# schematic.net
KiCad netlist of a schematic drawn in EasyEDA
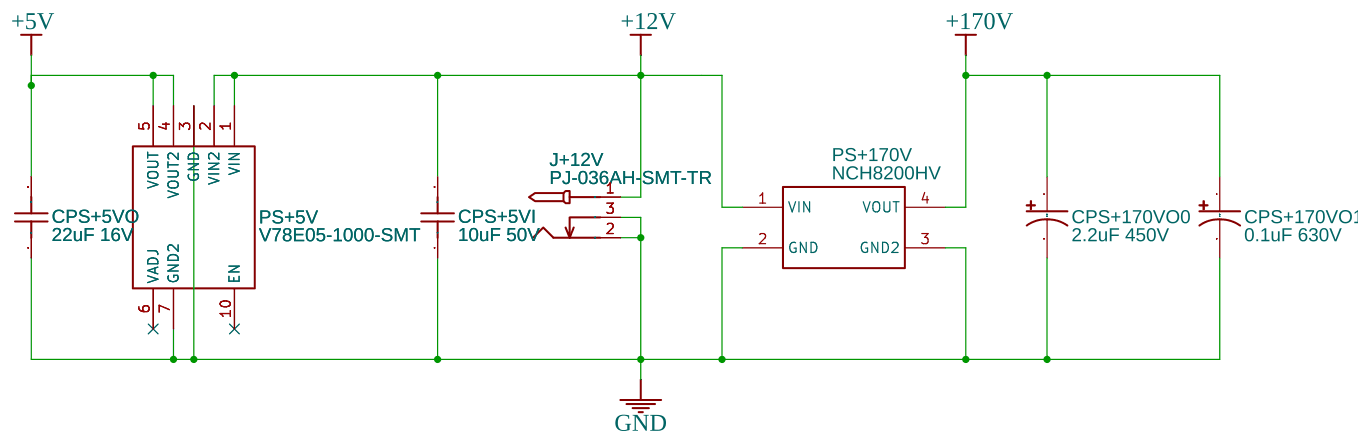
[diagram p0: power]
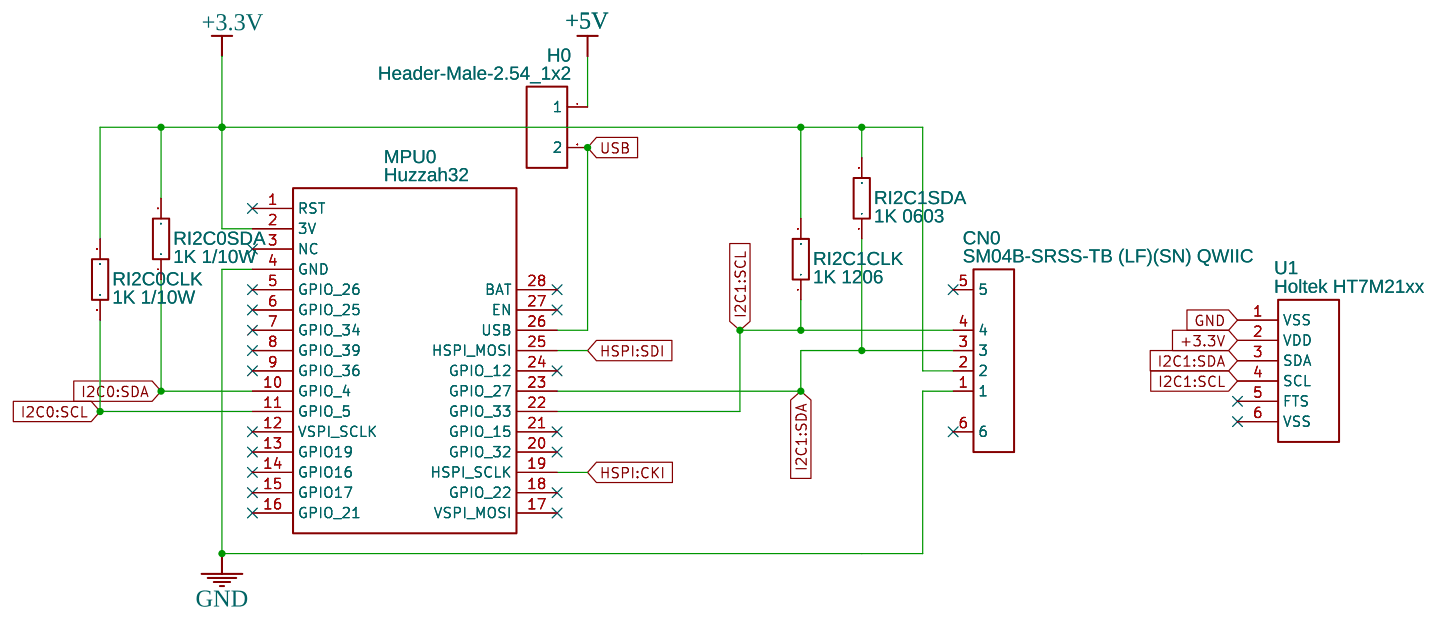
[diagram p1: smarts]
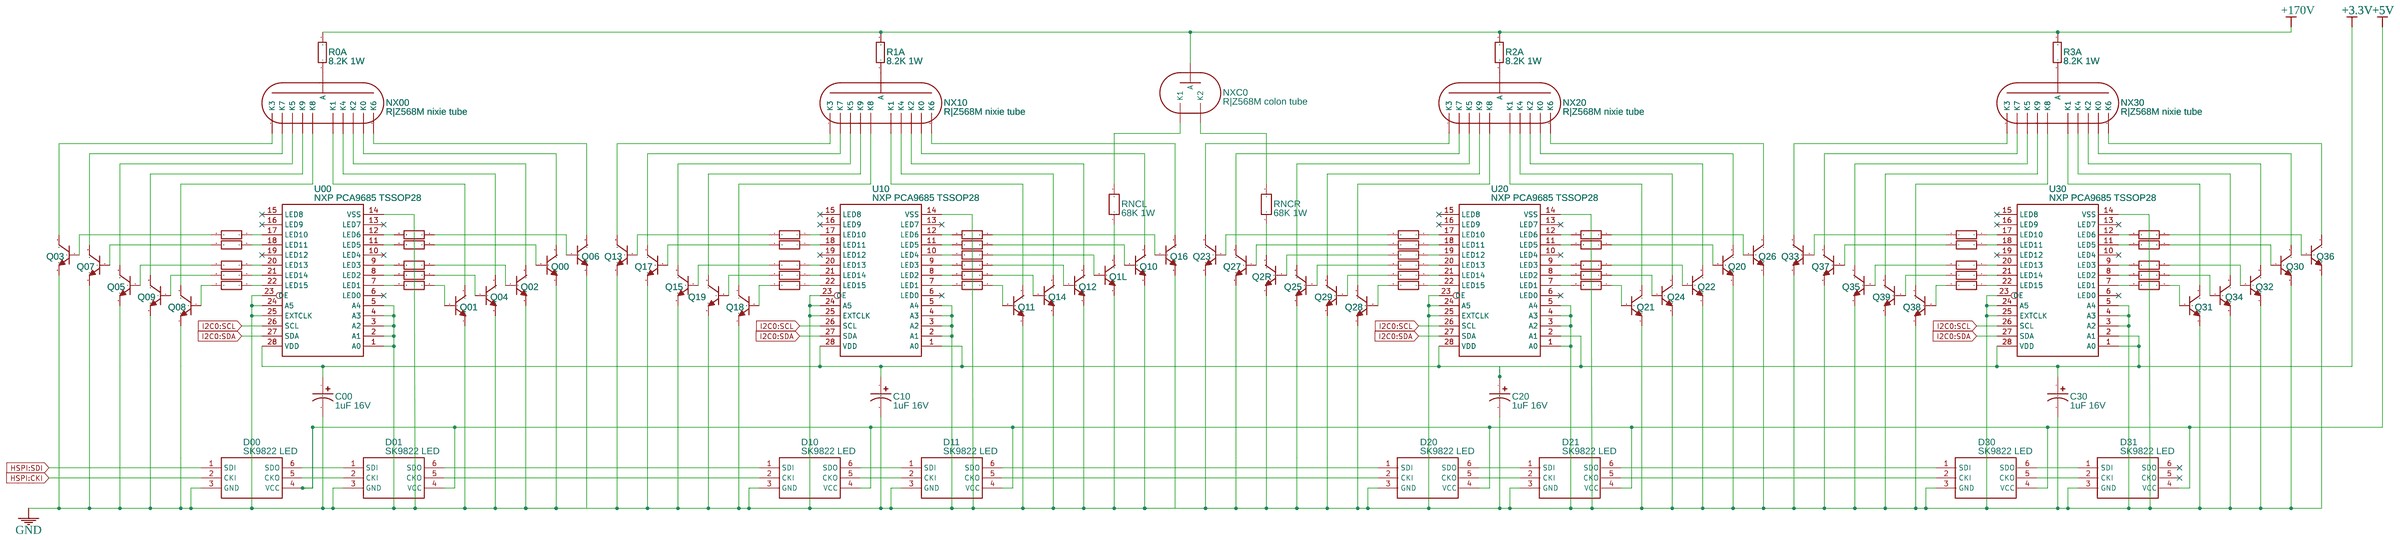
[diagram p2: nixies]

(export (version "E")
  (design (tool "Eeschema 10.0.6"))
  (components
    (comp (ref "CPS+5VI")
      (value "10uF 50V")
      (fields
        (field (name "BOM_Manufacturer Part") "C1210C106K5RACTU")
        (field (name "BOM_Supplier Part") "399-11629-1-ND")
      )
      (libsource (lib "") (part "CL32Y106KBJ4PNE"))
    )
    (comp (ref "CPS+5VO")
      (value "22uF 16V")
      (fields
        (field (name "BOM_Manufacturer Part") "C1210C226K4RAC7800")
        (field (name "BOM_Supplier Part") "399-11662-1-ND")
      )
      (libsource (lib "") (part "CL32A226KOJNNWE"))
    )
    (comp (ref "CPS+170VO0")
      (value "2.2uF 450V")
      (fields
        (field (name "BOM_Manufacturer Part") "C5750X6S2W225K250KA")
        (field (name "BOM_Supplier Part") "445-7781-1-ND")
      )
      (libsource (lib "") (part "ULV2G100MNL1GS_1"))
    )
    (comp (ref "CPS+170VO1")
      (value "0.1uF 630V")
      (fields
        (field (name "BOM_Manufacturer Part") "CGA8N4X7R2J104K230KA")
        (field (name "BOM_Supplier Part") "445-7922-1-ND")
      )
      (libsource (lib "") (part "ULV2G100MNL1GS"))
    )
    (comp (ref "J+12V")
      (value "PJ-036AH-SMT-TR")
      (fields (field (name "BOM_Supplier Part") "CP-036AHPJCT-ND"))
      (libsource (lib "") (part "DC005-2.0MM"))
    )
    (comp (ref "PS+5V")
      (value "V78E05-1000-SMT")
      (fields (field (name "BOM_Supplier Part") "102-5033-1-ND"))
      (libsource (lib "") (part "V78E05-1000-SMT"))
    )
    (comp (ref "PS+170V")
      (value "NCH8200HV")
      (fields (field (name "BOM_Supplier Part") "B074S2T7X3"))
      (libsource (lib "") (part "NCH8200HV"))
    )
    (comp (ref "CN0")
      (value "SM04B-SRSS-TB (LF)(SN) QWIIC")
      (fields
        (field (name "BOM_Manufacturer Part") "PRT-14417")
        (field (name "BOM_Supplier Part") "PRT-14417-ND")
      )
      (libsource (lib "") (part "SM04B-SRSS-TB (LF)(SN) QWIIC"))
    )
    (comp (ref "H0")
      (value "Header-Male-2.54_1x2")
      (fields
        (field (name "BOM_Manufacturer Part") "M20-8890245")
        (field (name "BOM_Supplier Part") "952-3231-ND")
      )
      (libsource (lib "") (part "Header-Male-2.54_1x2"))
    )
    (comp (ref "MPU0")
      (value "Huzzah32")
      (fields (field (name "BOM_Manufacturer Part") "3405") (field (name "BOM_Supplier Part") "1528-2181-ND"))
      (libsource (lib "") (part "Huzzah32"))
    )
    (comp (ref "RI2C0CLK")
      (value "1K 1/10W")
      (fields
        (field (name "BOM_Manufacturer Part") "CRCW06031K00FKEA")
        (field (name "BOM_Supplier Part") "541-1.00KHCT-ND")
      )
      (libsource (lib "") (part "CR0805-FX-1001ELF"))
    )
    (comp (ref "RI2C0SDA")
      (value "1K 1/10W")
      (fields
        (field (name "BOM_Manufacturer Part") "CRCW06031K00FKEA")
        (field (name "BOM_Supplier Part") "541-1.00KHCT-ND")
      )
      (libsource (lib "") (part "CR0805-FX-1001ELF_1"))
    )
    (comp (ref "RI2C1CLK")
      (value "1K 1206")
      (fields
        (field (name "BOM_Manufacturer Part") "RCL06121K00FKEA")
        (field (name "BOM_Supplier Part") "RCL1.00KCCT-ND")
      )
      (libsource (lib "") (part "CR0805-FX-1001ELF_3"))
    )
    (comp (ref "RI2C1SDA")
      (value "1K 0603")
      (fields
        (field (name "BOM_Manufacturer Part") "CRCW06031K00FKEA")
        (field (name "BOM_Supplier Part") "541-1.00KHCT-ND")
      )
      (libsource (lib "") (part "CR0805-FX-1001ELF_2"))
    )
    (comp (ref "U1")
      (value "Holtek HT7M21xx")
      (fields (field (name "BOM_Manufacturer Part") "HT7M21xx"))
      (libsource (lib "") (part "Holtek HT7M21xx"))
    )
    (comp (ref "C00")
      (value "1uF 16V")
      (fields
        (field (name "BOM_Manufacturer Part") "C0603C105K8RACTU")
        (field (name "BOM_Supplier Part") "399-11133-1-ND")
      )
      (libsource (lib "") (part "C_Tan_SMD_A_US"))
    )
    (comp (ref "C10")
      (value "1uF 16V")
      (fields
        (field (name "BOM_Manufacturer Part") "C0603C105K8RACTU")
        (field (name "BOM_Supplier Part") "399-11133-1-ND")
      )
      (libsource (lib "") (part "C_Tan_SMD_A_US"))
    )
    (comp (ref "C20")
      (value "1uF 16V")
      (fields
        (field (name "BOM_Manufacturer Part") "C0603C105K8RACTU")
        (field (name "BOM_Supplier Part") "399-11133-1-ND")
      )
      (libsource (lib "") (part "C_Tan_SMD_A_US_1"))
    )
    (comp (ref "C30")
      (value "1uF 16V")
      (fields
        (field (name "BOM_Manufacturer Part") "C0603C105K8RACTU")
        (field (name "BOM_Supplier Part") "399-11133-1-ND")
      )
      (libsource (lib "") (part "C_Tan_SMD_A_US"))
    )
    (comp (ref "D00")
      (value "SK9822 LED")
      (fields (field (name "BOM_Manufacturer Part") "2343") (field (name "BOM_Supplier Part") "1528-1436-ND"))
      (libsource (lib "") (part "SK9822 LED_1"))
    )
    (comp (ref "D01")
      (value "SK9822 LED")
      (fields (field (name "BOM_Manufacturer Part") "2343") (field (name "BOM_Supplier Part") "1528-1436-ND"))
      (libsource (lib "") (part "SK9822 LED_1"))
    )
    (comp (ref "D10")
      (value "SK9822 LED")
      (fields (field (name "BOM_Manufacturer Part") "2343") (field (name "BOM_Supplier Part") "1528-1436-ND"))
      (libsource (lib "") (part "SK9822 LED_1"))
    )
    (comp (ref "D11")
      (value "SK9822 LED")
      (fields (field (name "BOM_Manufacturer Part") "2343") (field (name "BOM_Supplier Part") "1528-1436-ND"))
      (libsource (lib "") (part "SK9822 LED_1"))
    )
    (comp (ref "D20")
      (value "SK9822 LED")
      (fields (field (name "BOM_Manufacturer Part") "2343") (field (name "BOM_Supplier Part") "1528-1436-ND"))
      (libsource (lib "") (part "SK9822 LED"))
    )
    (comp (ref "D21")
      (value "SK9822 LED")
      (fields (field (name "BOM_Manufacturer Part") "2343") (field (name "BOM_Supplier Part") "1528-1436-ND"))
      (libsource (lib "") (part "SK9822 LED"))
    )
    (comp (ref "D30")
      (value "SK9822 LED")
      (fields (field (name "BOM_Manufacturer Part") "2343") (field (name "BOM_Supplier Part") "1528-1436-ND"))
      (libsource (lib "") (part "SK9822 LED"))
    )
    (comp (ref "D31")
      (value "SK9822 LED")
      (fields (field (name "BOM_Manufacturer Part") "2343") (field (name "BOM_Supplier Part") "1528-1436-ND"))
      (libsource (lib "") (part "SK9822 LED"))
    )
    (comp (ref "NX00") (value "R|Z568M nixie tube") (libsource (lib "") (part "R|Z568M nixie tube")))
    (comp (ref "NX10") (value "R|Z568M nixie tube") (libsource (lib "") (part "R|Z568M nixie tube")))
    (comp (ref "NX20") (value "R|Z568M nixie tube") (libsource (lib "") (part "R|Z568M nixie tube")))
    (comp (ref "NX30") (value "R|Z568M nixie tube") (libsource (lib "") (part "R|Z568M nixie tube")))
    (comp (ref "NXC0") (value "R|Z568M colon tube") (libsource (lib "") (part "R|Z568M colon tube")))
    (comp (ref "Q00")
      (value "SMMBTA42LT1G")
      (fields (field (name "BOM_Supplier Part") "SMMBTA42LT1GOSCT-ND"))
      (libsource (lib "") (part "MMBTA42LT1G"))
    )
    (comp (ref "Q01")
      (value "SMMBTA42LT1G")
      (fields (field (name "BOM_Supplier Part") "SMMBTA42LT1GOSCT-ND"))
      (libsource (lib "") (part "MMBTA42LT1G"))
    )
    (comp (ref "Q1L")
      (value "SMMBTA42LT1G")
      (fields (field (name "BOM_Supplier Part") "SMMBTA42LT1GOSCT-ND"))
      (libsource (lib "") (part "MMBTA42LT1G_5"))
    )
    (comp (ref "Q02")
      (value "SMMBTA42LT1G")
      (fields (field (name "BOM_Supplier Part") "SMMBTA42LT1GOSCT-ND"))
      (libsource (lib "") (part "MMBTA42LT1G"))
    )
    (comp (ref "Q2R")
      (value "SMMBTA42LT1G")
      (fields (field (name "BOM_Supplier Part") "SMMBTA42LT1GOSCT-ND"))
      (libsource (lib "") (part "MMBTA42LT1G_3"))
    )
    (comp (ref "Q03")
      (value "SMMBTA42LT1G")
      (fields (field (name "BOM_Supplier Part") "SMMBTA42LT1GOSCT-ND"))
      (libsource (lib "") (part "MMBTA42LT1G_1"))
    )
    (comp (ref "Q04")
      (value "SMMBTA42LT1G")
      (fields (field (name "BOM_Supplier Part") "SMMBTA42LT1GOSCT-ND"))
      (libsource (lib "") (part "MMBTA42LT1G"))
    )
    (comp (ref "Q05")
      (value "SMMBTA42LT1G")
      (fields (field (name "BOM_Supplier Part") "SMMBTA42LT1GOSCT-ND"))
      (libsource (lib "") (part "MMBTA42LT1G_1"))
    )
    (comp (ref "Q06")
      (value "SMMBTA42LT1G")
      (fields (field (name "BOM_Supplier Part") "SMMBTA42LT1GOSCT-ND"))
      (libsource (lib "") (part "MMBTA42LT1G"))
    )
    (comp (ref "Q07")
      (value "SMMBTA42LT1G")
      (fields (field (name "BOM_Supplier Part") "SMMBTA42LT1GOSCT-ND"))
      (libsource (lib "") (part "MMBTA42LT1G_1"))
    )
    (comp (ref "Q08")
      (value "SMMBTA42LT1G")
      (fields (field (name "BOM_Supplier Part") "SMMBTA42LT1GOSCT-ND"))
      (libsource (lib "") (part "MMBTA42LT1G_1"))
    )
    (comp (ref "Q09")
      (value "SMMBTA42LT1G")
      (fields (field (name "BOM_Supplier Part") "SMMBTA42LT1GOSCT-ND"))
      (libsource (lib "") (part "MMBTA42LT1G_1"))
    )
    (comp (ref "Q10")
      (value "SMMBTA42LT1G")
      (fields (field (name "BOM_Supplier Part") "SMMBTA42LT1GOSCT-ND"))
      (libsource (lib "") (part "MMBTA42LT1G"))
    )
    (comp (ref "Q11")
      (value "SMMBTA42LT1G")
      (fields (field (name "BOM_Supplier Part") "SMMBTA42LT1GOSCT-ND"))
      (libsource (lib "") (part "MMBTA42LT1G"))
    )
    (comp (ref "Q12")
      (value "SMMBTA42LT1G")
      (fields (field (name "BOM_Supplier Part") "SMMBTA42LT1GOSCT-ND"))
      (libsource (lib "") (part "MMBTA42LT1G"))
    )
    (comp (ref "Q13")
      (value "SMMBTA42LT1G")
      (fields (field (name "BOM_Supplier Part") "SMMBTA42LT1GOSCT-ND"))
      (libsource (lib "") (part "MMBTA42LT1G_1"))
    )
    (comp (ref "Q14")
      (value "SMMBTA42LT1G")
      (fields (field (name "BOM_Supplier Part") "SMMBTA42LT1GOSCT-ND"))
      (libsource (lib "") (part "MMBTA42LT1G"))
    )
    (comp (ref "Q15")
      (value "SMMBTA42LT1G")
      (fields (field (name "BOM_Supplier Part") "SMMBTA42LT1GOSCT-ND"))
      (libsource (lib "") (part "MMBTA42LT1G_1"))
    )
    (comp (ref "Q16")
      (value "SMMBTA42LT1G")
      (fields (field (name "BOM_Supplier Part") "SMMBTA42LT1GOSCT-ND"))
      (libsource (lib "") (part "MMBTA42LT1G"))
    )
    (comp (ref "Q17")
      (value "SMMBTA42LT1G")
      (fields (field (name "BOM_Supplier Part") "SMMBTA42LT1GOSCT-ND"))
      (libsource (lib "") (part "MMBTA42LT1G_1"))
    )
    (comp (ref "Q18")
      (value "SMMBTA42LT1G")
      (fields (field (name "BOM_Supplier Part") "SMMBTA42LT1GOSCT-ND"))
      (libsource (lib "") (part "MMBTA42LT1G_1"))
    )
    (comp (ref "Q19")
      (value "SMMBTA42LT1G")
      (fields (field (name "BOM_Supplier Part") "SMMBTA42LT1GOSCT-ND"))
      (libsource (lib "") (part "MMBTA42LT1G_1"))
    )
    (comp (ref "Q20")
      (value "SMMBTA42LT1G")
      (fields (field (name "BOM_Supplier Part") "SMMBTA42LT1GOSCT-ND"))
      (libsource (lib "") (part "MMBTA42LT1G_2"))
    )
    (comp (ref "Q21")
      (value "SMMBTA42LT1G")
      (fields (field (name "BOM_Supplier Part") "SMMBTA42LT1GOSCT-ND"))
      (libsource (lib "") (part "MMBTA42LT1G_2"))
    )
    (comp (ref "Q22")
      (value "SMMBTA42LT1G")
      (fields (field (name "BOM_Supplier Part") "SMMBTA42LT1GOSCT-ND"))
      (libsource (lib "") (part "MMBTA42LT1G_2"))
    )
    (comp (ref "Q23")
      (value "SMMBTA42LT1G")
      (fields (field (name "BOM_Supplier Part") "SMMBTA42LT1GOSCT-ND"))
      (libsource (lib "") (part "MMBTA42LT1G_1"))
    )
    (comp (ref "Q24")
      (value "SMMBTA42LT1G")
      (fields (field (name "BOM_Supplier Part") "SMMBTA42LT1GOSCT-ND"))
      (libsource (lib "") (part "MMBTA42LT1G_2"))
    )
    (comp (ref "Q25")
      (value "SMMBTA42LT1G")
      (fields (field (name "BOM_Supplier Part") "SMMBTA42LT1GOSCT-ND"))
      (libsource (lib "") (part "MMBTA42LT1G_4"))
    )
    (comp (ref "Q26")
      (value "SMMBTA42LT1G")
      (fields (field (name "BOM_Supplier Part") "SMMBTA42LT1GOSCT-ND"))
      (libsource (lib "") (part "MMBTA42LT1G_2"))
    )
    (comp (ref "Q27")
      (value "SMMBTA42LT1G")
      (fields (field (name "BOM_Supplier Part") "SMMBTA42LT1GOSCT-ND"))
      (libsource (lib "") (part "MMBTA42LT1G_1"))
    )
    (comp (ref "Q28")
      (value "SMMBTA42LT1G")
      (fields (field (name "BOM_Supplier Part") "SMMBTA42LT1GOSCT-ND"))
      (libsource (lib "") (part "MMBTA42LT1G_4"))
    )
    (comp (ref "Q29")
      (value "SMMBTA42LT1G")
      (fields (field (name "BOM_Supplier Part") "SMMBTA42LT1GOSCT-ND"))
      (libsource (lib "") (part "MMBTA42LT1G_4"))
    )
    (comp (ref "Q30")
      (value "SMMBTA42LT1G")
      (fields (field (name "BOM_Supplier Part") "SMMBTA42LT1GOSCT-ND"))
      (libsource (lib "") (part "MMBTA42LT1G_2"))
    )
    (comp (ref "Q31")
      (value "SMMBTA42LT1G")
      (fields (field (name "BOM_Supplier Part") "SMMBTA42LT1GOSCT-ND"))
      (libsource (lib "") (part "MMBTA42LT1G_2"))
    )
    (comp (ref "Q32")
      (value "SMMBTA42LT1G")
      (fields (field (name "BOM_Supplier Part") "SMMBTA42LT1GOSCT-ND"))
      (libsource (lib "") (part "MMBTA42LT1G_2"))
    )
    (comp (ref "Q33")
      (value "SMMBTA42LT1G")
      (fields (field (name "BOM_Supplier Part") "SMMBTA42LT1GOSCT-ND"))
      (libsource (lib "") (part "MMBTA42LT1G_4"))
    )
    (comp (ref "Q34")
      (value "SMMBTA42LT1G")
      (fields (field (name "BOM_Supplier Part") "SMMBTA42LT1GOSCT-ND"))
      (libsource (lib "") (part "MMBTA42LT1G_2"))
    )
    (comp (ref "Q35")
      (value "SMMBTA42LT1G")
      (fields (field (name "BOM_Supplier Part") "SMMBTA42LT1GOSCT-ND"))
      (libsource (lib "") (part "MMBTA42LT1G_4"))
    )
    (comp (ref "Q36")
      (value "SMMBTA42LT1G")
      (fields (field (name "BOM_Supplier Part") "SMMBTA42LT1GOSCT-ND"))
      (libsource (lib "") (part "MMBTA42LT1G_2"))
    )
    (comp (ref "Q37")
      (value "SMMBTA42LT1G")
      (fields (field (name "BOM_Supplier Part") "SMMBTA42LT1GOSCT-ND"))
      (libsource (lib "") (part "MMBTA42LT1G_4"))
    )
    (comp (ref "Q38")
      (value "SMMBTA42LT1G")
      (fields (field (name "BOM_Supplier Part") "SMMBTA42LT1GOSCT-ND"))
      (libsource (lib "") (part "MMBTA42LT1G_4"))
    )
    (comp (ref "Q39")
      (value "SMMBTA42LT1G")
      (fields (field (name "BOM_Supplier Part") "SMMBTA42LT1GOSCT-ND"))
      (libsource (lib "") (part "MMBTA42LT1G_4"))
    )
    (comp (ref "R00")
      (value "1K 1/10W")
      (fields
        (field (name "BOM_Manufacturer Part") "CRCW06031K00FKEA")
        (field (name "BOM_Supplier Part") "541-1.00KHCT-ND")
      )
      (libsource (lib "") (part "CR0805-FX-1001ELF"))
    )
    (comp (ref "R0A")
      (value "8.2K 1W")
      (fields
        (field (name "BOM_Manufacturer Part") "CRCW25128K20JNEG")
        (field (name "BOM_Supplier Part") "541-8.2KXCT-ND")
      )
      (libsource (lib "") (part "CR2512F8K2E04_3"))
    )
    (comp (ref "R01")
      (value "1K 1/10W")
      (fields
        (field (name "BOM_Manufacturer Part") "CRCW06031K00FKEA")
        (field (name "BOM_Supplier Part") "541-1.00KHCT-ND")
      )
      (libsource (lib "") (part "CR0805-FX-1001ELF"))
    )
    (comp (ref "R1A")
      (value "8.2K 1W")
      (fields
        (field (name "BOM_Manufacturer Part") "CRCW25128K20JNEG")
        (field (name "BOM_Supplier Part") "541-8.2KXCT-ND")
      )
      (libsource (lib "") (part "CR2512F8K2E04"))
    )
    (comp (ref "R1L")
      (value "1K 1/10W")
      (fields
        (field (name "BOM_Manufacturer Part") "CRCW06031K00FKEA")
        (field (name "BOM_Supplier Part") "541-1.00KHCT-ND")
      )
      (libsource (lib "") (part "CR0805-FX-1001ELF_1"))
    )
    (comp (ref "R02")
      (value "1K 1/10W")
      (fields
        (field (name "BOM_Manufacturer Part") "CRCW06031K00FKEA")
        (field (name "BOM_Supplier Part") "541-1.00KHCT-ND")
      )
      (libsource (lib "") (part "CR0805-FX-1001ELF"))
    )
    (comp (ref "R2A")
      (value "8.2K 1W")
      (fields
        (field (name "BOM_Manufacturer Part") "CRCW25128K20JNEG")
        (field (name "BOM_Supplier Part") "541-8.2KXCT-ND")
      )
      (libsource (lib "") (part "CR2512F8K2E04_2"))
    )
    (comp (ref "R2R")
      (value "1K 1/10W")
      (fields
        (field (name "BOM_Manufacturer Part") "CRCW06031K00FKEA")
        (field (name "BOM_Supplier Part") "541-1.00KHCT-ND")
      )
      (libsource (lib "") (part "CR0805-FX-1001ELF_2"))
    )
    (comp (ref "R03")
      (value "1K 1/10W")
      (fields
        (field (name "BOM_Manufacturer Part") "CRCW06031K00FKEA")
        (field (name "BOM_Supplier Part") "541-1.00KHCT-ND")
      )
      (libsource (lib "") (part "CR0805-FX-1001ELF"))
    )
    (comp (ref "R3A")
      (value "8.2K 1W")
      (fields
        (field (name "BOM_Manufacturer Part") "CRCW25128K20JNEG")
        (field (name "BOM_Supplier Part") "541-8.2KXCT-ND")
      )
      (libsource (lib "") (part "CR2512F8K2E04_1"))
    )
    (comp (ref "R04")
      (value "1K 1/10W")
      (fields
        (field (name "BOM_Manufacturer Part") "CRCW06031K00FKEA")
        (field (name "BOM_Supplier Part") "541-1.00KHCT-ND")
      )
      (libsource (lib "") (part "CR0805-FX-1001ELF"))
    )
    (comp (ref "R05")
      (value "1K 1/10W")
      (fields
        (field (name "BOM_Manufacturer Part") "CRCW06031K00FKEA")
        (field (name "BOM_Supplier Part") "541-1.00KHCT-ND")
      )
      (libsource (lib "") (part "CR0805-FX-1001ELF"))
    )
    (comp (ref "R06")
      (value "1K 1/10W")
      (fields
        (field (name "BOM_Manufacturer Part") "CRCW06031K00FKEA")
        (field (name "BOM_Supplier Part") "541-1.00KHCT-ND")
      )
      (libsource (lib "") (part "CR0805-FX-1001ELF"))
    )
    (comp (ref "R07")
      (value "1K 1/10W")
      (fields
        (field (name "BOM_Manufacturer Part") "CRCW06031K00FKEA")
        (field (name "BOM_Supplier Part") "541-1.00KHCT-ND")
      )
      (libsource (lib "") (part "CR0805-FX-1001ELF"))
    )
    (comp (ref "R08")
      (value "1K 1/10W")
      (fields
        (field (name "BOM_Manufacturer Part") "CRCW06031K00FKEA")
        (field (name "BOM_Supplier Part") "541-1.00KHCT-ND")
      )
      (libsource (lib "") (part "CR0805-FX-1001ELF"))
    )
    (comp (ref "R09")
      (value "1K 1/10W")
      (fields
        (field (name "BOM_Manufacturer Part") "CRCW06031K00FKEA")
        (field (name "BOM_Supplier Part") "541-1.00KHCT-ND")
      )
      (libsource (lib "") (part "CR0805-FX-1001ELF"))
    )
    (comp (ref "R10")
      (value "1K 1/10W")
      (fields
        (field (name "BOM_Manufacturer Part") "CRCW06031K00FKEA")
        (field (name "BOM_Supplier Part") "541-1.00KHCT-ND")
      )
      (libsource (lib "") (part "CR0805-FX-1001ELF"))
    )
    (comp (ref "R11")
      (value "1K 1/10W")
      (fields
        (field (name "BOM_Manufacturer Part") "CRCW06031K00FKEA")
        (field (name "BOM_Supplier Part") "541-1.00KHCT-ND")
      )
      (libsource (lib "") (part "CR0805-FX-1001ELF"))
    )
    (comp (ref "R12")
      (value "1K 1/10W")
      (fields
        (field (name "BOM_Manufacturer Part") "CRCW06031K00FKEA")
        (field (name "BOM_Supplier Part") "541-1.00KHCT-ND")
      )
      (libsource (lib "") (part "CR0805-FX-1001ELF"))
    )
    (comp (ref "R13")
      (value "1K 1/10W")
      (fields
        (field (name "BOM_Manufacturer Part") "CRCW06031K00FKEA")
        (field (name "BOM_Supplier Part") "541-1.00KHCT-ND")
      )
      (libsource (lib "") (part "CR0805-FX-1001ELF"))
    )
    (comp (ref "R14")
      (value "1K 1/10W")
      (fields
        (field (name "BOM_Manufacturer Part") "CRCW06031K00FKEA")
        (field (name "BOM_Supplier Part") "541-1.00KHCT-ND")
      )
      (libsource (lib "") (part "CR0805-FX-1001ELF"))
    )
    (comp (ref "R15")
      (value "1K 1/10W")
      (fields
        (field (name "BOM_Manufacturer Part") "CRCW06031K00FKEA")
        (field (name "BOM_Supplier Part") "541-1.00KHCT-ND")
      )
      (libsource (lib "") (part "CR0805-FX-1001ELF"))
    )
    (comp (ref "R16")
      (value "1K 1/10W")
      (fields
        (field (name "BOM_Manufacturer Part") "CRCW06031K00FKEA")
        (field (name "BOM_Supplier Part") "541-1.00KHCT-ND")
      )
      (libsource (lib "") (part "CR0805-FX-1001ELF"))
    )
    (comp (ref "R17")
      (value "1K 1/10W")
      (fields
        (field (name "BOM_Manufacturer Part") "CRCW06031K00FKEA")
        (field (name "BOM_Supplier Part") "541-1.00KHCT-ND")
      )
      (libsource (lib "") (part "CR0805-FX-1001ELF"))
    )
    (comp (ref "R18")
      (value "1K 1/10W")
      (fields
        (field (name "BOM_Manufacturer Part") "CRCW06031K00FKEA")
        (field (name "BOM_Supplier Part") "541-1.00KHCT-ND")
      )
      (libsource (lib "") (part "CR0805-FX-1001ELF"))
    )
    (comp (ref "R19")
      (value "1K 1/10W")
      (fields
        (field (name "BOM_Manufacturer Part") "CRCW06031K00FKEA")
        (field (name "BOM_Supplier Part") "541-1.00KHCT-ND")
      )
      (libsource (lib "") (part "CR0805-FX-1001ELF"))
    )
    (comp (ref "R20")
      (value "1K 1/10W")
      (fields
        (field (name "BOM_Manufacturer Part") "CRCW06031K00FKEA")
        (field (name "BOM_Supplier Part") "541-1.00KHCT-ND")
      )
      (libsource (lib "") (part "CR0805-FX-1001ELF"))
    )
    (comp (ref "R21")
      (value "1K 1/10W")
      (fields
        (field (name "BOM_Manufacturer Part") "CRCW06031K00FKEA")
        (field (name "BOM_Supplier Part") "541-1.00KHCT-ND")
      )
      (libsource (lib "") (part "CR0805-FX-1001ELF"))
    )
    (comp (ref "R22")
      (value "1K 1/10W")
      (fields
        (field (name "BOM_Manufacturer Part") "CRCW06031K00FKEA")
        (field (name "BOM_Supplier Part") "541-1.00KHCT-ND")
      )
      (libsource (lib "") (part "CR0805-FX-1001ELF"))
    )
    (comp (ref "R23")
      (value "1K 1/10W")
      (fields
        (field (name "BOM_Manufacturer Part") "CRCW06031K00FKEA")
        (field (name "BOM_Supplier Part") "541-1.00KHCT-ND")
      )
      (libsource (lib "") (part "CR0805-FX-1001ELF"))
    )
    (comp (ref "R24")
      (value "1K 1/10W")
      (fields
        (field (name "BOM_Manufacturer Part") "CRCW06031K00FKEA")
        (field (name "BOM_Supplier Part") "541-1.00KHCT-ND")
      )
      (libsource (lib "") (part "CR0805-FX-1001ELF"))
    )
    (comp (ref "R25")
      (value "1K 1/10W")
      (fields
        (field (name "BOM_Manufacturer Part") "CRCW06031K00FKEA")
        (field (name "BOM_Supplier Part") "541-1.00KHCT-ND")
      )
      (libsource (lib "") (part "CR0805-FX-1001ELF"))
    )
    (comp (ref "R26")
      (value "1K 1/10W")
      (fields
        (field (name "BOM_Manufacturer Part") "CRCW06031K00FKEA")
        (field (name "BOM_Supplier Part") "541-1.00KHCT-ND")
      )
      (libsource (lib "") (part "CR0805-FX-1001ELF"))
    )
    (comp (ref "R27")
      (value "1K 1/10W")
      (fields
        (field (name "BOM_Manufacturer Part") "CRCW06031K00FKEA")
        (field (name "BOM_Supplier Part") "541-1.00KHCT-ND")
      )
      (libsource (lib "") (part "CR0805-FX-1001ELF"))
    )
    (comp (ref "R28")
      (value "1K 1/10W")
      (fields
        (field (name "BOM_Manufacturer Part") "CRCW06031K00FKEA")
        (field (name "BOM_Supplier Part") "541-1.00KHCT-ND")
      )
      (libsource (lib "") (part "CR0805-FX-1001ELF"))
    )
    (comp (ref "R29")
      (value "1K 1/10W")
      (fields
        (field (name "BOM_Manufacturer Part") "CRCW06031K00FKEA")
        (field (name "BOM_Supplier Part") "541-1.00KHCT-ND")
      )
      (libsource (lib "") (part "CR0805-FX-1001ELF"))
    )
    (comp (ref "R30")
      (value "1K 1/10W")
      (fields
        (field (name "BOM_Manufacturer Part") "CRCW06031K00FKEA")
        (field (name "BOM_Supplier Part") "541-1.00KHCT-ND")
      )
      (libsource (lib "") (part "CR0805-FX-1001ELF"))
    )
    (comp (ref "R31")
      (value "1K 1/10W")
      (fields
        (field (name "BOM_Manufacturer Part") "CRCW06031K00FKEA")
        (field (name "BOM_Supplier Part") "541-1.00KHCT-ND")
      )
      (libsource (lib "") (part "CR0805-FX-1001ELF"))
    )
    (comp (ref "R32")
      (value "1K 1/10W")
      (fields
        (field (name "BOM_Manufacturer Part") "CRCW06031K00FKEA")
        (field (name "BOM_Supplier Part") "541-1.00KHCT-ND")
      )
      (libsource (lib "") (part "CR0805-FX-1001ELF"))
    )
    (comp (ref "R33")
      (value "1K 1/10W")
      (fields
        (field (name "BOM_Manufacturer Part") "CRCW06031K00FKEA")
        (field (name "BOM_Supplier Part") "541-1.00KHCT-ND")
      )
      (libsource (lib "") (part "CR0805-FX-1001ELF"))
    )
    (comp (ref "R34")
      (value "1K 1/10W")
      (fields
        (field (name "BOM_Manufacturer Part") "CRCW06031K00FKEA")
        (field (name "BOM_Supplier Part") "541-1.00KHCT-ND")
      )
      (libsource (lib "") (part "CR0805-FX-1001ELF"))
    )
    (comp (ref "R35")
      (value "1K 1/10W")
      (fields
        (field (name "BOM_Manufacturer Part") "CRCW06031K00FKEA")
        (field (name "BOM_Supplier Part") "541-1.00KHCT-ND")
      )
      (libsource (lib "") (part "CR0805-FX-1001ELF"))
    )
    (comp (ref "R36")
      (value "1K 1/10W")
      (fields
        (field (name "BOM_Manufacturer Part") "CRCW06031K00FKEA")
        (field (name "BOM_Supplier Part") "541-1.00KHCT-ND")
      )
      (libsource (lib "") (part "CR0805-FX-1001ELF"))
    )
    (comp (ref "R37")
      (value "1K 1/10W")
      (fields
        (field (name "BOM_Manufacturer Part") "CRCW06031K00FKEA")
        (field (name "BOM_Supplier Part") "541-1.00KHCT-ND")
      )
      (libsource (lib "") (part "CR0805-FX-1001ELF"))
    )
    (comp (ref "R38")
      (value "1K 1/10W")
      (fields
        (field (name "BOM_Manufacturer Part") "CRCW06031K00FKEA")
        (field (name "BOM_Supplier Part") "541-1.00KHCT-ND")
      )
      (libsource (lib "") (part "CR0805-FX-1001ELF"))
    )
    (comp (ref "R39")
      (value "1K 1/10W")
      (fields
        (field (name "BOM_Manufacturer Part") "CRCW06031K00FKEA")
        (field (name "BOM_Supplier Part") "541-1.00KHCT-ND")
      )
      (libsource (lib "") (part "CR0805-FX-1001ELF"))
    )
    (comp (ref "RNCL")
      (value "68K 1W")
      (fields
        (field (name "BOM_Manufacturer Part") "CRCW251268K0JNEG")
        (field (name "BOM_Supplier Part") "541-68KXCT-ND")
      )
      (libsource (lib "") (part "CR2512F68K0E04Z_1"))
    )
    (comp (ref "RNCR")
      (value "68K 1W")
      (fields
        (field (name "BOM_Manufacturer Part") "CRCW251268K0JNEG")
        (field (name "BOM_Supplier Part") "541-68KXCT-ND")
      )
      (libsource (lib "") (part "CR2512F68K0E04Z"))
    )
    (comp (ref "U00")
      (value "NXP PCA9685 TSSOP28")
      (fields
        (field (name "BOM_Manufacturer Part") "PCA9685PW/Q900,118")
        (field (name "BOM_Supplier Part") "568-5931-1-ND")
      )
      (libsource (lib "") (part "NXP PCA9685 TSSOP28"))
    )
    (comp (ref "U10")
      (value "NXP PCA9685 TSSOP28")
      (fields
        (field (name "BOM_Manufacturer Part") "PCA9685PW/Q900,118")
        (field (name "BOM_Supplier Part") "568-5931-1-ND")
      )
      (libsource (lib "") (part "NXP PCA9685 TSSOP28"))
    )
    (comp (ref "U20")
      (value "NXP PCA9685 TSSOP28")
      (fields
        (field (name "BOM_Manufacturer Part") "PCA9685PW/Q900,118")
        (field (name "BOM_Supplier Part") "568-5931-1-ND")
      )
      (libsource (lib "") (part "NXP PCA9685 TSSOP28"))
    )
    (comp (ref "U30")
      (value "NXP PCA9685 TSSOP28")
      (fields
        (field (name "BOM_Manufacturer Part") "PCA9685PW/Q900,118")
        (field (name "BOM_Supplier Part") "568-5931-1-ND")
      )
      (libsource (lib "") (part "NXP PCA9685 TSSOP28"))
    )
  )
  (nets
    (net (code "1") (name "+3.3V") (class "Default")
      (node (ref "C00") (pin "1") (pinfunction "1_1") (pintype "unspecified"))
      (node (ref "C10") (pin "1") (pinfunction "1_1") (pintype "unspecified"))
      (node (ref "C20") (pin "1") (pinfunction "1_1") (pintype "unspecified"))
      (node (ref "C30") (pin "1") (pinfunction "1_1") (pintype "unspecified"))
      (node (ref "CN0") (pin "2") (pinfunction "2_2") (pintype "unspecified"))
      (node (ref "MPU0") (pin "2") (pinfunction "3V_2") (pintype "unspecified"))
      (node (ref "RI2C0CLK") (pin "2") (pinfunction "2_2") (pintype "unspecified"))
      (node (ref "RI2C0SDA") (pin "2") (pinfunction "2_2") (pintype "unspecified"))
      (node (ref "RI2C1CLK") (pin "2") (pinfunction "2_2") (pintype "unspecified"))
      (node (ref "RI2C1SDA") (pin "2") (pinfunction "2_2") (pintype "unspecified"))
      (node (ref "U00") (pin "28") (pinfunction "VDD_28") (pintype "unspecified"))
      (node (ref "U1") (pin "2") (pinfunction "VDD_2") (pintype "unspecified"))
      (node (ref "U10") (pin "1") (pinfunction "A0_1") (pintype "unspecified"))
      (node (ref "U10") (pin "28") (pinfunction "VDD_28") (pintype "unspecified"))
      (node (ref "U20") (pin "2") (pinfunction "A1_2") (pintype "unspecified"))
      (node (ref "U20") (pin "28") (pinfunction "VDD_28") (pintype "unspecified"))
      (node (ref "U30") (pin "1") (pinfunction "A0_1") (pintype "unspecified"))
      (node (ref "U30") (pin "2") (pinfunction "A1_2") (pintype "unspecified"))
      (node (ref "U30") (pin "28") (pinfunction "VDD_28") (pintype "unspecified"))
    )
    (net (code "2") (name "+5V") (class "Default")
      (node (ref "CPS+5VO") (pin "2") (pinfunction "2_2") (pintype "unspecified"))
      (node (ref "D00") (pin "4") (pinfunction "VCC_4") (pintype "unspecified"))
      (node (ref "D01") (pin "4") (pinfunction "VCC_4") (pintype "unspecified"))
      (node (ref "D10") (pin "4") (pinfunction "VCC_4") (pintype "unspecified"))
      (node (ref "D11") (pin "4") (pinfunction "VCC_4") (pintype "unspecified"))
      (node (ref "D20") (pin "4") (pinfunction "VCC_4") (pintype "unspecified"))
      (node (ref "D21") (pin "4") (pinfunction "VCC_4") (pintype "unspecified"))
      (node (ref "D30") (pin "4") (pinfunction "VCC_4") (pintype "unspecified"))
      (node (ref "D31") (pin "4") (pinfunction "VCC_4") (pintype "unspecified"))
      (node (ref "H0") (pin "1") (pinfunction "1_1") (pintype "unspecified"))
      (node (ref "PS+5V") (pin "4") (pinfunction "VOUT2_4") (pintype "unspecified"))
      (node (ref "PS+5V") (pin "5") (pinfunction "VOUT_5") (pintype "unspecified"))
    )
    (net (code "3") (name "+12V") (class "Default")
      (node (ref "CPS+5VI") (pin "2") (pinfunction "2_2") (pintype "unspecified"))
      (node (ref "J+12V") (pin "1") (pinfunction "1_1") (pintype "unspecified"))
      (node (ref "PS+170V") (pin "1") (pinfunction "VIN_1") (pintype "unspecified"))
      (node (ref "PS+5V") (pin "1") (pinfunction "VIN_1") (pintype "unspecified"))
      (node (ref "PS+5V") (pin "2") (pinfunction "VIN2_2") (pintype "unspecified"))
    )
    (net (code "4") (name "+170V") (class "Default")
      (node (ref "CPS+170VO0") (pin "1") (pinfunction "1_1") (pintype "unspecified"))
      (node (ref "CPS+170VO1") (pin "1") (pinfunction "1_1") (pintype "unspecified"))
      (node (ref "NXC0") (pin "2") (pinfunction "A_2") (pintype "unspecified"))
      (node (ref "PS+170V") (pin "4") (pinfunction "VOUT_4") (pintype "unspecified"))
      (node (ref "R0A") (pin "2") (pinfunction "2_2") (pintype "unspecified"))
      (node (ref "R1A") (pin "2") (pinfunction "2_2") (pintype "unspecified"))
      (node (ref "R2A") (pin "2") (pinfunction "2_2") (pintype "unspecified"))
      (node (ref "R3A") (pin "2") (pinfunction "2_2") (pintype "unspecified"))
    )
    (net (code "5") (name "GND") (class "Default")
      (node (ref "C00") (pin "2") (pinfunction "2_2") (pintype "unspecified"))
      (node (ref "C10") (pin "2") (pinfunction "2_2") (pintype "unspecified"))
      (node (ref "C20") (pin "2") (pinfunction "2_2") (pintype "unspecified"))
      (node (ref "C30") (pin "2") (pinfunction "2_2") (pintype "unspecified"))
      (node (ref "CN0") (pin "1") (pinfunction "1_1") (pintype "unspecified"))
      (node (ref "CPS+170VO0") (pin "2") (pinfunction "2_2") (pintype "unspecified"))
      (node (ref "CPS+170VO1") (pin "2") (pinfunction "2_2") (pintype "unspecified"))
      (node (ref "CPS+5VI") (pin "1") (pinfunction "1_1") (pintype "unspecified"))
      (node (ref "CPS+5VO") (pin "1") (pinfunction "1_1") (pintype "unspecified"))
      (node (ref "D00") (pin "3") (pinfunction "GND_3") (pintype "unspecified"))
      (node (ref "D01") (pin "3") (pinfunction "GND_3") (pintype "unspecified"))
      (node (ref "D10") (pin "3") (pinfunction "GND_3") (pintype "unspecified"))
      (node (ref "D11") (pin "3") (pinfunction "GND_3") (pintype "unspecified"))
      (node (ref "D20") (pin "3") (pinfunction "GND_3") (pintype "unspecified"))
      (node (ref "D21") (pin "3") (pinfunction "GND_3") (pintype "unspecified"))
      (node (ref "D30") (pin "3") (pinfunction "GND_3") (pintype "unspecified"))
      (node (ref "D31") (pin "3") (pinfunction "GND_3") (pintype "unspecified"))
      (node (ref "J+12V") (pin "2") (pinfunction "2_2") (pintype "unspecified"))
      (node (ref "J+12V") (pin "3") (pinfunction "3_3") (pintype "unspecified"))
      (node (ref "MPU0") (pin "4") (pinfunction "GND_4") (pintype "unspecified"))
      (node (ref "PS+170V") (pin "2") (pinfunction "GND_2") (pintype "unspecified"))
      (node (ref "PS+170V") (pin "3") (pinfunction "GND2_3") (pintype "unspecified"))
      (node (ref "PS+5V") (pin "3") (pinfunction "GND_3") (pintype "unspecified"))
      (node (ref "PS+5V") (pin "7") (pinfunction "GND2_7") (pintype "unspecified"))
      (node (ref "Q00") (pin "2") (pinfunction "2_2") (pintype "input"))
      (node (ref "Q01") (pin "2") (pinfunction "2_2") (pintype "input"))
      (node (ref "Q02") (pin "2") (pinfunction "2_2") (pintype "input"))
      (node (ref "Q03") (pin "2") (pinfunction "2_2") (pintype "input"))
      (node (ref "Q04") (pin "2") (pinfunction "2_2") (pintype "input"))
      (node (ref "Q05") (pin "2") (pinfunction "2_2") (pintype "input"))
      (node (ref "Q06") (pin "2") (pinfunction "2_2") (pintype "input"))
      (node (ref "Q07") (pin "2") (pinfunction "2_2") (pintype "input"))
      (node (ref "Q08") (pin "2") (pinfunction "2_2") (pintype "input"))
      (node (ref "Q09") (pin "2") (pinfunction "2_2") (pintype "input"))
      (node (ref "Q10") (pin "2") (pinfunction "2_2") (pintype "input"))
      (node (ref "Q11") (pin "2") (pinfunction "2_2") (pintype "input"))
      (node (ref "Q12") (pin "2") (pinfunction "2_2") (pintype "input"))
      (node (ref "Q13") (pin "2") (pinfunction "2_2") (pintype "input"))
      (node (ref "Q14") (pin "2") (pinfunction "2_2") (pintype "input"))
      (node (ref "Q15") (pin "2") (pinfunction "2_2") (pintype "input"))
      (node (ref "Q16") (pin "2") (pinfunction "2_2") (pintype "input"))
      (node (ref "Q17") (pin "2") (pinfunction "2_2") (pintype "input"))
      (node (ref "Q18") (pin "2") (pinfunction "2_2") (pintype "input"))
      (node (ref "Q19") (pin "2") (pinfunction "2_2") (pintype "input"))
      (node (ref "Q1L") (pin "2") (pinfunction "2_2") (pintype "input"))
      (node (ref "Q20") (pin "2") (pinfunction "2_2") (pintype "input"))
      (node (ref "Q21") (pin "2") (pinfunction "2_2") (pintype "input"))
      (node (ref "Q22") (pin "2") (pinfunction "2_2") (pintype "input"))
      (node (ref "Q23") (pin "2") (pinfunction "2_2") (pintype "input"))
      (node (ref "Q24") (pin "2") (pinfunction "2_2") (pintype "input"))
      (node (ref "Q25") (pin "2") (pinfunction "2_2") (pintype "input"))
      (node (ref "Q26") (pin "2") (pinfunction "2_2") (pintype "input"))
      (node (ref "Q27") (pin "2") (pinfunction "2_2") (pintype "input"))
      (node (ref "Q28") (pin "2") (pinfunction "2_2") (pintype "input"))
      (node (ref "Q29") (pin "2") (pinfunction "2_2") (pintype "input"))
      (node (ref "Q2R") (pin "2") (pinfunction "2_2") (pintype "input"))
      (node (ref "Q30") (pin "2") (pinfunction "2_2") (pintype "input"))
      (node (ref "Q31") (pin "2") (pinfunction "2_2") (pintype "input"))
      (node (ref "Q32") (pin "2") (pinfunction "2_2") (pintype "input"))
      (node (ref "Q33") (pin "2") (pinfunction "2_2") (pintype "input"))
      (node (ref "Q34") (pin "2") (pinfunction "2_2") (pintype "input"))
      (node (ref "Q35") (pin "2") (pinfunction "2_2") (pintype "input"))
      (node (ref "Q36") (pin "2") (pinfunction "2_2") (pintype "input"))
      (node (ref "Q37") (pin "2") (pinfunction "2_2") (pintype "input"))
      (node (ref "Q38") (pin "2") (pinfunction "2_2") (pintype "input"))
      (node (ref "Q39") (pin "2") (pinfunction "2_2") (pintype "input"))
      (node (ref "U00") (pin "1") (pinfunction "A0_1") (pintype "unspecified"))
      (node (ref "U00") (pin "14") (pinfunction "VSS_14") (pintype "unspecified"))
      (node (ref "U00") (pin "2") (pinfunction "A1_2") (pintype "unspecified"))
      (node (ref "U00") (pin "23") (pinfunction "OE_23") (pintype "unspecified"))
      (node (ref "U00") (pin "24") (pinfunction "A5_24") (pintype "unspecified"))
      (node (ref "U00") (pin "25") (pinfunction "EXTCLK_25") (pintype "unspecified"))
      (node (ref "U00") (pin "3") (pinfunction "A2_3") (pintype "unspecified"))
      (node (ref "U00") (pin "4") (pinfunction "A3_4") (pintype "unspecified"))
      (node (ref "U00") (pin "5") (pinfunction "A4_5") (pintype "unspecified"))
      (node (ref "U1") (pin "1") (pinfunction "VSS_1") (pintype "unspecified"))
      (node (ref "U10") (pin "14") (pinfunction "VSS_14") (pintype "unspecified"))
      (node (ref "U10") (pin "2") (pinfunction "A1_2") (pintype "unspecified"))
      (node (ref "U10") (pin "23") (pinfunction "OE_23") (pintype "unspecified"))
      (node (ref "U10") (pin "24") (pinfunction "A5_24") (pintype "unspecified"))
      (node (ref "U10") (pin "25") (pinfunction "EXTCLK_25") (pintype "unspecified"))
      (node (ref "U10") (pin "3") (pinfunction "A2_3") (pintype "unspecified"))
      (node (ref "U10") (pin "4") (pinfunction "A3_4") (pintype "unspecified"))
      (node (ref "U10") (pin "5") (pinfunction "A4_5") (pintype "unspecified"))
      (node (ref "U20") (pin "1") (pinfunction "A0_1") (pintype "unspecified"))
      (node (ref "U20") (pin "14") (pinfunction "VSS_14") (pintype "unspecified"))
      (node (ref "U20") (pin "23") (pinfunction "OE_23") (pintype "unspecified"))
      (node (ref "U20") (pin "24") (pinfunction "A5_24") (pintype "unspecified"))
      (node (ref "U20") (pin "25") (pinfunction "EXTCLK_25") (pintype "unspecified"))
      (node (ref "U20") (pin "3") (pinfunction "A2_3") (pintype "unspecified"))
      (node (ref "U20") (pin "4") (pinfunction "A3_4") (pintype "unspecified"))
      (node (ref "U20") (pin "5") (pinfunction "A4_5") (pintype "unspecified"))
      (node (ref "U30") (pin "14") (pinfunction "VSS_14") (pintype "unspecified"))
      (node (ref "U30") (pin "23") (pinfunction "OE_23") (pintype "unspecified"))
      (node (ref "U30") (pin "24") (pinfunction "A5_24") (pintype "unspecified"))
      (node (ref "U30") (pin "25") (pinfunction "EXTCLK_25") (pintype "unspecified"))
      (node (ref "U30") (pin "3") (pinfunction "A2_3") (pintype "unspecified"))
      (node (ref "U30") (pin "4") (pinfunction "A3_4") (pintype "unspecified"))
      (node (ref "U30") (pin "5") (pinfunction "A4_5") (pintype "unspecified"))
    )
    (net (code "6") (name "HSPI:CKI") (class "Default")
      (node (ref "D00") (pin "2") (pinfunction "CKI_2") (pintype "unspecified"))
      (node (ref "MPU0") (pin "19") (pinfunction "HSPI_SCLK_19") (pintype "unspecified"))
    )
    (net (code "7") (name "HSPI:SDI") (class "Default")
      (node (ref "D00") (pin "1") (pinfunction "SDI_1") (pintype "unspecified"))
      (node (ref "MPU0") (pin "25") (pinfunction "HSPI_MOSI_25") (pintype "unspecified"))
    )
    (net (code "8") (name "I2C0:SCL") (class "Default")
      (node (ref "MPU0") (pin "11") (pinfunction "GPIO_5_11") (pintype "unspecified"))
      (node (ref "RI2C0CLK") (pin "1") (pinfunction "1_1") (pintype "unspecified"))
      (node (ref "U00") (pin "26") (pinfunction "SCL_26") (pintype "unspecified"))
      (node (ref "U10") (pin "26") (pinfunction "SCL_26") (pintype "unspecified"))
      (node (ref "U20") (pin "26") (pinfunction "SCL_26") (pintype "unspecified"))
      (node (ref "U30") (pin "26") (pinfunction "SCL_26") (pintype "unspecified"))
    )
    (net (code "9") (name "I2C0:SDA") (class "Default")
      (node (ref "MPU0") (pin "10") (pinfunction "GPIO_4_10") (pintype "unspecified"))
      (node (ref "RI2C0SDA") (pin "1") (pinfunction "1_1") (pintype "unspecified"))
      (node (ref "U00") (pin "27") (pinfunction "SDA_27") (pintype "unspecified"))
      (node (ref "U10") (pin "27") (pinfunction "SDA_27") (pintype "unspecified"))
      (node (ref "U20") (pin "27") (pinfunction "SDA_27") (pintype "unspecified"))
      (node (ref "U30") (pin "27") (pinfunction "SDA_27") (pintype "unspecified"))
    )
    (net (code "10") (name "I2C1:SCL") (class "Default")
      (node (ref "CN0") (pin "4") (pinfunction "4_4") (pintype "unspecified"))
      (node (ref "MPU0") (pin "22") (pinfunction "GPIO_33_22") (pintype "unspecified"))
      (node (ref "RI2C1CLK") (pin "1") (pinfunction "1_1") (pintype "unspecified"))
      (node (ref "U1") (pin "4") (pinfunction "SCL_4") (pintype "unspecified"))
    )
    (net (code "11") (name "I2C1:SDA") (class "Default")
      (node (ref "CN0") (pin "3") (pinfunction "3_3") (pintype "unspecified"))
      (node (ref "MPU0") (pin "23") (pinfunction "GPIO_27_23") (pintype "unspecified"))
      (node (ref "RI2C1SDA") (pin "1") (pinfunction "1_1") (pintype "unspecified"))
      (node (ref "U1") (pin "3") (pinfunction "SDA_3") (pintype "unspecified"))
    )
    (net (code "12") (name "Net-(D00-CKO)") (class "Default")
      (node (ref "D00") (pin "5") (pinfunction "CKO_5") (pintype "unspecified"))
      (node (ref "D01") (pin "2") (pinfunction "CKI_2") (pintype "unspecified"))
    )
    (net (code "13") (name "Net-(D00-SDO)") (class "Default")
      (node (ref "D00") (pin "6") (pinfunction "SDO_6") (pintype "unspecified"))
      (node (ref "D01") (pin "1") (pinfunction "SDI_1") (pintype "unspecified"))
    )
    (net (code "14") (name "Net-(D01-CKO)") (class "Default")
      (node (ref "D01") (pin "5") (pinfunction "CKO_5") (pintype "unspecified"))
      (node (ref "D10") (pin "2") (pinfunction "CKI_2") (pintype "unspecified"))
    )
    (net (code "15") (name "Net-(D01-SDO)") (class "Default")
      (node (ref "D01") (pin "6") (pinfunction "SDO_6") (pintype "unspecified"))
      (node (ref "D10") (pin "1") (pinfunction "SDI_1") (pintype "unspecified"))
    )
    (net (code "16") (name "Net-(D10-CKO)") (class "Default")
      (node (ref "D10") (pin "5") (pinfunction "CKO_5") (pintype "unspecified"))
      (node (ref "D11") (pin "2") (pinfunction "CKI_2") (pintype "unspecified"))
    )
    (net (code "17") (name "Net-(D10-SDO)") (class "Default")
      (node (ref "D10") (pin "6") (pinfunction "SDO_6") (pintype "unspecified"))
      (node (ref "D11") (pin "1") (pinfunction "SDI_1") (pintype "unspecified"))
    )
    (net (code "18") (name "Net-(D11-CKO)") (class "Default")
      (node (ref "D11") (pin "5") (pinfunction "CKO_5") (pintype "unspecified"))
      (node (ref "D20") (pin "2") (pinfunction "CKI_2") (pintype "unspecified"))
    )
    (net (code "19") (name "Net-(D11-SDO)") (class "Default")
      (node (ref "D11") (pin "6") (pinfunction "SDO_6") (pintype "unspecified"))
      (node (ref "D20") (pin "1") (pinfunction "SDI_1") (pintype "unspecified"))
    )
    (net (code "20") (name "Net-(D20-CKO)") (class "Default")
      (node (ref "D20") (pin "5") (pinfunction "CKO_5") (pintype "unspecified"))
      (node (ref "D21") (pin "2") (pinfunction "CKI_2") (pintype "unspecified"))
    )
    (net (code "21") (name "Net-(D20-SDO)") (class "Default")
      (node (ref "D20") (pin "6") (pinfunction "SDO_6") (pintype "unspecified"))
      (node (ref "D21") (pin "1") (pinfunction "SDI_1") (pintype "unspecified"))
    )
    (net (code "22") (name "Net-(D21-CKO)") (class "Default")
      (node (ref "D21") (pin "5") (pinfunction "CKO_5") (pintype "unspecified"))
      (node (ref "D30") (pin "2") (pinfunction "CKI_2") (pintype "unspecified"))
    )
    (net (code "23") (name "Net-(D21-SDO)") (class "Default")
      (node (ref "D21") (pin "6") (pinfunction "SDO_6") (pintype "unspecified"))
      (node (ref "D30") (pin "1") (pinfunction "SDI_1") (pintype "unspecified"))
    )
    (net (code "24") (name "Net-(D30-CKO)") (class "Default")
      (node (ref "D30") (pin "5") (pinfunction "CKO_5") (pintype "unspecified"))
      (node (ref "D31") (pin "2") (pinfunction "CKI_2") (pintype "unspecified"))
    )
    (net (code "25") (name "Net-(D30-SDO)") (class "Default")
      (node (ref "D30") (pin "6") (pinfunction "SDO_6") (pintype "unspecified"))
      (node (ref "D31") (pin "1") (pinfunction "SDI_1") (pintype "unspecified"))
    )
    (net (code "26") (name "Net-(NX00-A)") (class "Default")
      (node (ref "NX00") (pin "6") (pinfunction "A_6") (pintype "unspecified"))
      (node (ref "R0A") (pin "1") (pinfunction "1_1") (pintype "unspecified"))
    )
    (net (code "27") (name "Net-(NX00-K0)") (class "Default")
      (node (ref "NX00") (pin "4") (pinfunction "K0_4") (pintype "unspecified"))
      (node (ref "Q00") (pin "3") (pinfunction "3_3") (pintype "input"))
    )
    (net (code "28") (name "Net-(NX00-K1)") (class "Default")
      (node (ref "NX00") (pin "1") (pinfunction "K1_1") (pintype "passive"))
      (node (ref "Q01") (pin "3") (pinfunction "3_3") (pintype "input"))
    )
    (net (code "29") (name "Net-(NX00-K2)") (class "Default")
      (node (ref "NX00") (pin "3") (pinfunction "K2_3") (pintype "unspecified"))
      (node (ref "Q02") (pin "3") (pinfunction "3_3") (pintype "input"))
    )
    (net (code "30") (name "Net-(NX00-K3)") (class "Default")
      (node (ref "NX00") (pin "7") (pinfunction "K3_7") (pintype "unspecified"))
      (node (ref "Q03") (pin "3") (pinfunction "3_3") (pintype "input"))
    )
    (net (code "31") (name "Net-(NX00-K4)") (class "Default")
      (node (ref "NX00") (pin "2") (pinfunction "K4_2") (pintype "unspecified"))
      (node (ref "Q04") (pin "3") (pinfunction "3_3") (pintype "input"))
    )
    (net (code "32") (name "Net-(NX00-K5)") (class "Default")
      (node (ref "NX00") (pin "9") (pinfunction "K5_9") (pintype "unspecified"))
      (node (ref "Q05") (pin "3") (pinfunction "3_3") (pintype "input"))
    )
    (net (code "33") (name "Net-(NX00-K6)") (class "Default")
      (node (ref "NX00") (pin "5") (pinfunction "K6_5") (pintype "unspecified"))
      (node (ref "Q06") (pin "3") (pinfunction "3_3") (pintype "input"))
    )
    (net (code "34") (name "Net-(NX00-K7)") (class "Default")
      (node (ref "NX00") (pin "8") (pinfunction "K7_8") (pintype "unspecified"))
      (node (ref "Q07") (pin "3") (pinfunction "3_3") (pintype "input"))
    )
    (net (code "35") (name "Net-(NX00-K8)") (class "Default")
      (node (ref "NX00") (pin "11") (pinfunction "K8_11") (pintype "unspecified"))
      (node (ref "Q08") (pin "3") (pinfunction "3_3") (pintype "input"))
    )
    (net (code "36") (name "Net-(NX00-K9)") (class "Default")
      (node (ref "NX00") (pin "10") (pinfunction "K9_10") (pintype "unspecified"))
      (node (ref "Q09") (pin "3") (pinfunction "3_3") (pintype "input"))
    )
    (net (code "37") (name "Net-(NX10-A)") (class "Default")
      (node (ref "NX10") (pin "6") (pinfunction "A_6") (pintype "unspecified"))
      (node (ref "R1A") (pin "1") (pinfunction "1_1") (pintype "unspecified"))
    )
    (net (code "38") (name "Net-(NX10-K0)") (class "Default")
      (node (ref "NX10") (pin "4") (pinfunction "K0_4") (pintype "unspecified"))
      (node (ref "Q10") (pin "3") (pinfunction "3_3") (pintype "input"))
    )
    (net (code "39") (name "Net-(NX10-K1)") (class "Default")
      (node (ref "NX10") (pin "1") (pinfunction "K1_1") (pintype "passive"))
      (node (ref "Q11") (pin "3") (pinfunction "3_3") (pintype "input"))
    )
    (net (code "40") (name "Net-(NX10-K2)") (class "Default")
      (node (ref "NX10") (pin "3") (pinfunction "K2_3") (pintype "unspecified"))
      (node (ref "Q12") (pin "3") (pinfunction "3_3") (pintype "input"))
    )
    (net (code "41") (name "Net-(NX10-K3)") (class "Default")
      (node (ref "NX10") (pin "7") (pinfunction "K3_7") (pintype "unspecified"))
      (node (ref "Q13") (pin "3") (pinfunction "3_3") (pintype "input"))
    )
    (net (code "42") (name "Net-(NX10-K4)") (class "Default")
      (node (ref "NX10") (pin "2") (pinfunction "K4_2") (pintype "unspecified"))
      (node (ref "Q14") (pin "3") (pinfunction "3_3") (pintype "input"))
    )
    (net (code "43") (name "Net-(NX10-K5)") (class "Default")
      (node (ref "NX10") (pin "9") (pinfunction "K5_9") (pintype "unspecified"))
      (node (ref "Q15") (pin "3") (pinfunction "3_3") (pintype "input"))
    )
    (net (code "44") (name "Net-(NX10-K6)") (class "Default")
      (node (ref "NX10") (pin "5") (pinfunction "K6_5") (pintype "unspecified"))
      (node (ref "Q16") (pin "3") (pinfunction "3_3") (pintype "input"))
    )
    (net (code "45") (name "Net-(NX10-K7)") (class "Default")
      (node (ref "NX10") (pin "8") (pinfunction "K7_8") (pintype "unspecified"))
      (node (ref "Q17") (pin "3") (pinfunction "3_3") (pintype "input"))
    )
    (net (code "46") (name "Net-(NX10-K8)") (class "Default")
      (node (ref "NX10") (pin "11") (pinfunction "K8_11") (pintype "unspecified"))
      (node (ref "Q18") (pin "3") (pinfunction "3_3") (pintype "input"))
    )
    (net (code "47") (name "Net-(NX10-K9)") (class "Default")
      (node (ref "NX10") (pin "10") (pinfunction "K9_10") (pintype "unspecified"))
      (node (ref "Q19") (pin "3") (pinfunction "3_3") (pintype "input"))
    )
    (net (code "48") (name "Net-(NX20-A)") (class "Default")
      (node (ref "NX20") (pin "6") (pinfunction "A_6") (pintype "unspecified"))
      (node (ref "R2A") (pin "1") (pinfunction "1_1") (pintype "unspecified"))
    )
    (net (code "49") (name "Net-(NX20-K0)") (class "Default")
      (node (ref "NX20") (pin "4") (pinfunction "K0_4") (pintype "unspecified"))
      (node (ref "Q20") (pin "3") (pinfunction "3_3") (pintype "input"))
    )
    (net (code "50") (name "Net-(NX20-K1)") (class "Default")
      (node (ref "NX20") (pin "1") (pinfunction "K1_1") (pintype "passive"))
      (node (ref "Q21") (pin "3") (pinfunction "3_3") (pintype "input"))
    )
    (net (code "51") (name "Net-(NX20-K2)") (class "Default")
      (node (ref "NX20") (pin "3") (pinfunction "K2_3") (pintype "unspecified"))
      (node (ref "Q22") (pin "3") (pinfunction "3_3") (pintype "input"))
    )
    (net (code "52") (name "Net-(NX20-K3)") (class "Default")
      (node (ref "NX20") (pin "7") (pinfunction "K3_7") (pintype "unspecified"))
      (node (ref "Q23") (pin "3") (pinfunction "3_3") (pintype "input"))
    )
    (net (code "53") (name "Net-(NX20-K4)") (class "Default")
      (node (ref "NX20") (pin "2") (pinfunction "K4_2") (pintype "unspecified"))
      (node (ref "Q24") (pin "3") (pinfunction "3_3") (pintype "input"))
    )
    (net (code "54") (name "Net-(NX20-K5)") (class "Default")
      (node (ref "NX20") (pin "9") (pinfunction "K5_9") (pintype "unspecified"))
      (node (ref "Q25") (pin "3") (pinfunction "3_3") (pintype "input"))
    )
    (net (code "55") (name "Net-(NX20-K6)") (class "Default")
      (node (ref "NX20") (pin "5") (pinfunction "K6_5") (pintype "unspecified"))
      (node (ref "Q26") (pin "3") (pinfunction "3_3") (pintype "input"))
    )
    (net (code "56") (name "Net-(NX20-K7)") (class "Default")
      (node (ref "NX20") (pin "8") (pinfunction "K7_8") (pintype "unspecified"))
      (node (ref "Q27") (pin "3") (pinfunction "3_3") (pintype "input"))
    )
    (net (code "57") (name "Net-(NX20-K8)") (class "Default")
      (node (ref "NX20") (pin "11") (pinfunction "K8_11") (pintype "unspecified"))
      (node (ref "Q28") (pin "3") (pinfunction "3_3") (pintype "input"))
    )
    (net (code "58") (name "Net-(NX20-K9)") (class "Default")
      (node (ref "NX20") (pin "10") (pinfunction "K9_10") (pintype "unspecified"))
      (node (ref "Q29") (pin "3") (pinfunction "3_3") (pintype "input"))
    )
    (net (code "59") (name "Net-(NX30-A)") (class "Default")
      (node (ref "NX30") (pin "6") (pinfunction "A_6") (pintype "unspecified"))
      (node (ref "R3A") (pin "1") (pinfunction "1_1") (pintype "unspecified"))
    )
    (net (code "60") (name "Net-(NX30-K0)") (class "Default")
      (node (ref "NX30") (pin "4") (pinfunction "K0_4") (pintype "unspecified"))
      (node (ref "Q30") (pin "3") (pinfunction "3_3") (pintype "input"))
    )
    (net (code "61") (name "Net-(NX30-K1)") (class "Default")
      (node (ref "NX30") (pin "1") (pinfunction "K1_1") (pintype "passive"))
      (node (ref "Q31") (pin "3") (pinfunction "3_3") (pintype "input"))
    )
    (net (code "62") (name "Net-(NX30-K2)") (class "Default")
      (node (ref "NX30") (pin "3") (pinfunction "K2_3") (pintype "unspecified"))
      (node (ref "Q32") (pin "3") (pinfunction "3_3") (pintype "input"))
    )
    (net (code "63") (name "Net-(NX30-K3)") (class "Default")
      (node (ref "NX30") (pin "7") (pinfunction "K3_7") (pintype "unspecified"))
      (node (ref "Q33") (pin "3") (pinfunction "3_3") (pintype "input"))
    )
    (net (code "64") (name "Net-(NX30-K4)") (class "Default")
      (node (ref "NX30") (pin "2") (pinfunction "K4_2") (pintype "unspecified"))
      (node (ref "Q34") (pin "3") (pinfunction "3_3") (pintype "input"))
    )
    (net (code "65") (name "Net-(NX30-K5)") (class "Default")
      (node (ref "NX30") (pin "9") (pinfunction "K5_9") (pintype "unspecified"))
      (node (ref "Q35") (pin "3") (pinfunction "3_3") (pintype "input"))
    )
    (net (code "66") (name "Net-(NX30-K6)") (class "Default")
      (node (ref "NX30") (pin "5") (pinfunction "K6_5") (pintype "unspecified"))
      (node (ref "Q36") (pin "3") (pinfunction "3_3") (pintype "input"))
    )
    (net (code "67") (name "Net-(NX30-K7)") (class "Default")
      (node (ref "NX30") (pin "8") (pinfunction "K7_8") (pintype "unspecified"))
      (node (ref "Q37") (pin "3") (pinfunction "3_3") (pintype "input"))
    )
    (net (code "68") (name "Net-(NX30-K8)") (class "Default")
      (node (ref "NX30") (pin "11") (pinfunction "K8_11") (pintype "unspecified"))
      (node (ref "Q38") (pin "3") (pinfunction "3_3") (pintype "input"))
    )
    (net (code "69") (name "Net-(NX30-K9)") (class "Default")
      (node (ref "NX30") (pin "10") (pinfunction "K9_10") (pintype "unspecified"))
      (node (ref "Q39") (pin "3") (pinfunction "3_3") (pintype "input"))
    )
    (net (code "70") (name "Net-(NXC0-K1)") (class "Default")
      (node (ref "NXC0") (pin "3") (pinfunction "K1_3") (pintype "unspecified"))
      (node (ref "RNCL") (pin "2") (pinfunction "2_2") (pintype "unspecified"))
    )
    (net (code "71") (name "Net-(NXC0-K2)") (class "Default")
      (node (ref "NXC0") (pin "1") (pinfunction "K2_1") (pintype "unspecified"))
      (node (ref "RNCR") (pin "2") (pinfunction "2_2") (pintype "unspecified"))
    )
    (net (code "72") (name "Net-(Q00-Pad1)") (class "Default")
      (node (ref "Q00") (pin "1") (pinfunction "1_1") (pintype "input"))
      (node (ref "R00") (pin "1") (pinfunction "1_1") (pintype "unspecified"))
    )
    (net (code "73") (name "Net-(Q01-Pad1)") (class "Default")
      (node (ref "Q01") (pin "1") (pinfunction "1_1") (pintype "input"))
      (node (ref "R01") (pin "1") (pinfunction "1_1") (pintype "unspecified"))
    )
    (net (code "74") (name "Net-(Q1L-Pad1)") (class "Default")
      (node (ref "Q1L") (pin "1") (pinfunction "1_1") (pintype "input"))
      (node (ref "R1L") (pin "1") (pinfunction "1_1") (pintype "unspecified"))
    )
    (net (code "75") (name "Net-(Q1L-Pad3)") (class "Default")
      (node (ref "Q1L") (pin "3") (pinfunction "3_3") (pintype "input"))
      (node (ref "RNCL") (pin "1") (pinfunction "1_1") (pintype "unspecified"))
    )
    (net (code "76") (name "Net-(Q02-Pad1)") (class "Default")
      (node (ref "Q02") (pin "1") (pinfunction "1_1") (pintype "input"))
      (node (ref "R02") (pin "1") (pinfunction "1_1") (pintype "unspecified"))
    )
    (net (code "77") (name "Net-(Q2R-Pad1)") (class "Default")
      (node (ref "Q2R") (pin "1") (pinfunction "1_1") (pintype "input"))
      (node (ref "R2R") (pin "2") (pinfunction "2_2") (pintype "unspecified"))
    )
    (net (code "78") (name "Net-(Q2R-Pad3)") (class "Default")
      (node (ref "Q2R") (pin "3") (pinfunction "3_3") (pintype "input"))
      (node (ref "RNCR") (pin "1") (pinfunction "1_1") (pintype "unspecified"))
    )
    (net (code "79") (name "Net-(Q03-Pad1)") (class "Default")
      (node (ref "Q03") (pin "1") (pinfunction "1_1") (pintype "input"))
      (node (ref "R03") (pin "2") (pinfunction "2_2") (pintype "unspecified"))
    )
    (net (code "80") (name "Net-(Q04-Pad1)") (class "Default")
      (node (ref "Q04") (pin "1") (pinfunction "1_1") (pintype "input"))
      (node (ref "R04") (pin "1") (pinfunction "1_1") (pintype "unspecified"))
    )
    (net (code "81") (name "Net-(Q05-Pad1)") (class "Default")
      (node (ref "Q05") (pin "1") (pinfunction "1_1") (pintype "input"))
      (node (ref "R05") (pin "2") (pinfunction "2_2") (pintype "unspecified"))
    )
    (net (code "82") (name "Net-(Q06-Pad1)") (class "Default")
      (node (ref "Q06") (pin "1") (pinfunction "1_1") (pintype "input"))
      (node (ref "R06") (pin "1") (pinfunction "1_1") (pintype "unspecified"))
    )
    (net (code "83") (name "Net-(Q07-Pad1)") (class "Default")
      (node (ref "Q07") (pin "1") (pinfunction "1_1") (pintype "input"))
      (node (ref "R07") (pin "2") (pinfunction "2_2") (pintype "unspecified"))
    )
    (net (code "84") (name "Net-(Q08-Pad1)") (class "Default")
      (node (ref "Q08") (pin "1") (pinfunction "1_1") (pintype "input"))
      (node (ref "R08") (pin "2") (pinfunction "2_2") (pintype "unspecified"))
    )
    (net (code "85") (name "Net-(Q09-Pad1)") (class "Default")
      (node (ref "Q09") (pin "1") (pinfunction "1_1") (pintype "input"))
      (node (ref "R09") (pin "2") (pinfunction "2_2") (pintype "unspecified"))
    )
    (net (code "86") (name "Net-(Q10-Pad1)") (class "Default")
      (node (ref "Q10") (pin "1") (pinfunction "1_1") (pintype "input"))
      (node (ref "R10") (pin "1") (pinfunction "1_1") (pintype "unspecified"))
    )
    (net (code "87") (name "Net-(Q11-Pad1)") (class "Default")
      (node (ref "Q11") (pin "1") (pinfunction "1_1") (pintype "input"))
      (node (ref "R11") (pin "1") (pinfunction "1_1") (pintype "unspecified"))
    )
    (net (code "88") (name "Net-(Q12-Pad1)") (class "Default")
      (node (ref "Q12") (pin "1") (pinfunction "1_1") (pintype "input"))
      (node (ref "R12") (pin "1") (pinfunction "1_1") (pintype "unspecified"))
    )
    (net (code "89") (name "Net-(Q13-Pad1)") (class "Default")
      (node (ref "Q13") (pin "1") (pinfunction "1_1") (pintype "input"))
      (node (ref "R13") (pin "2") (pinfunction "2_2") (pintype "unspecified"))
    )
    (net (code "90") (name "Net-(Q14-Pad1)") (class "Default")
      (node (ref "Q14") (pin "1") (pinfunction "1_1") (pintype "input"))
      (node (ref "R14") (pin "1") (pinfunction "1_1") (pintype "unspecified"))
    )
    (net (code "91") (name "Net-(Q15-Pad1)") (class "Default")
      (node (ref "Q15") (pin "1") (pinfunction "1_1") (pintype "input"))
      (node (ref "R15") (pin "2") (pinfunction "2_2") (pintype "unspecified"))
    )
    (net (code "92") (name "Net-(Q16-Pad1)") (class "Default")
      (node (ref "Q16") (pin "1") (pinfunction "1_1") (pintype "input"))
      (node (ref "R16") (pin "1") (pinfunction "1_1") (pintype "unspecified"))
    )
    (net (code "93") (name "Net-(Q17-Pad1)") (class "Default")
      (node (ref "Q17") (pin "1") (pinfunction "1_1") (pintype "input"))
      (node (ref "R17") (pin "2") (pinfunction "2_2") (pintype "unspecified"))
    )
    (net (code "94") (name "Net-(Q18-Pad1)") (class "Default")
      (node (ref "Q18") (pin "1") (pinfunction "1_1") (pintype "input"))
      (node (ref "R18") (pin "2") (pinfunction "2_2") (pintype "unspecified"))
    )
    (net (code "95") (name "Net-(Q19-Pad1)") (class "Default")
      (node (ref "Q19") (pin "1") (pinfunction "1_1") (pintype "input"))
      (node (ref "R19") (pin "2") (pinfunction "2_2") (pintype "unspecified"))
    )
    (net (code "96") (name "Net-(Q20-Pad1)") (class "Default")
      (node (ref "Q20") (pin "1") (pinfunction "1_1") (pintype "input"))
      (node (ref "R20") (pin "1") (pinfunction "1_1") (pintype "unspecified"))
    )
    (net (code "97") (name "Net-(Q21-Pad1)") (class "Default")
      (node (ref "Q21") (pin "1") (pinfunction "1_1") (pintype "input"))
      (node (ref "R21") (pin "1") (pinfunction "1_1") (pintype "unspecified"))
    )
    (net (code "98") (name "Net-(Q22-Pad1)") (class "Default")
      (node (ref "Q22") (pin "1") (pinfunction "1_1") (pintype "input"))
      (node (ref "R22") (pin "1") (pinfunction "1_1") (pintype "unspecified"))
    )
    (net (code "99") (name "Net-(Q23-Pad1)") (class "Default")
      (node (ref "Q23") (pin "1") (pinfunction "1_1") (pintype "input"))
      (node (ref "R23") (pin "2") (pinfunction "2_2") (pintype "unspecified"))
    )
    (net (code "100") (name "Net-(Q24-Pad1)") (class "Default")
      (node (ref "Q24") (pin "1") (pinfunction "1_1") (pintype "input"))
      (node (ref "R24") (pin "1") (pinfunction "1_1") (pintype "unspecified"))
    )
    (net (code "101") (name "Net-(Q25-Pad1)") (class "Default")
      (node (ref "Q25") (pin "1") (pinfunction "1_1") (pintype "input"))
      (node (ref "R25") (pin "2") (pinfunction "2_2") (pintype "unspecified"))
    )
    (net (code "102") (name "Net-(Q26-Pad1)") (class "Default")
      (node (ref "Q26") (pin "1") (pinfunction "1_1") (pintype "input"))
      (node (ref "R26") (pin "1") (pinfunction "1_1") (pintype "unspecified"))
    )
    (net (code "103") (name "Net-(Q27-Pad1)") (class "Default")
      (node (ref "Q27") (pin "1") (pinfunction "1_1") (pintype "input"))
      (node (ref "R27") (pin "2") (pinfunction "2_2") (pintype "unspecified"))
    )
    (net (code "104") (name "Net-(Q28-Pad1)") (class "Default")
      (node (ref "Q28") (pin "1") (pinfunction "1_1") (pintype "input"))
      (node (ref "R28") (pin "2") (pinfunction "2_2") (pintype "unspecified"))
    )
    (net (code "105") (name "Net-(Q29-Pad1)") (class "Default")
      (node (ref "Q29") (pin "1") (pinfunction "1_1") (pintype "input"))
      (node (ref "R29") (pin "2") (pinfunction "2_2") (pintype "unspecified"))
    )
    (net (code "106") (name "Net-(Q30-Pad1)") (class "Default")
      (node (ref "Q30") (pin "1") (pinfunction "1_1") (pintype "input"))
      (node (ref "R30") (pin "1") (pinfunction "1_1") (pintype "unspecified"))
    )
    (net (code "107") (name "Net-(Q31-Pad1)") (class "Default")
      (node (ref "Q31") (pin "1") (pinfunction "1_1") (pintype "input"))
      (node (ref "R31") (pin "1") (pinfunction "1_1") (pintype "unspecified"))
    )
    (net (code "108") (name "Net-(Q32-Pad1)") (class "Default")
      (node (ref "Q32") (pin "1") (pinfunction "1_1") (pintype "input"))
      (node (ref "R32") (pin "1") (pinfunction "1_1") (pintype "unspecified"))
    )
    (net (code "109") (name "Net-(Q33-Pad1)") (class "Default")
      (node (ref "Q33") (pin "1") (pinfunction "1_1") (pintype "input"))
      (node (ref "R33") (pin "2") (pinfunction "2_2") (pintype "unspecified"))
    )
    (net (code "110") (name "Net-(Q34-Pad1)") (class "Default")
      (node (ref "Q34") (pin "1") (pinfunction "1_1") (pintype "input"))
      (node (ref "R34") (pin "1") (pinfunction "1_1") (pintype "unspecified"))
    )
    (net (code "111") (name "Net-(Q35-Pad1)") (class "Default")
      (node (ref "Q35") (pin "1") (pinfunction "1_1") (pintype "input"))
      (node (ref "R35") (pin "2") (pinfunction "2_2") (pintype "unspecified"))
    )
    (net (code "112") (name "Net-(Q36-Pad1)") (class "Default")
      (node (ref "Q36") (pin "1") (pinfunction "1_1") (pintype "input"))
      (node (ref "R36") (pin "1") (pinfunction "1_1") (pintype "unspecified"))
    )
    (net (code "113") (name "Net-(Q37-Pad1)") (class "Default")
      (node (ref "Q37") (pin "1") (pinfunction "1_1") (pintype "input"))
      (node (ref "R37") (pin "2") (pinfunction "2_2") (pintype "unspecified"))
    )
    (net (code "114") (name "Net-(Q38-Pad1)") (class "Default")
      (node (ref "Q38") (pin "1") (pinfunction "1_1") (pintype "input"))
      (node (ref "R38") (pin "2") (pinfunction "2_2") (pintype "unspecified"))
    )
    (net (code "115") (name "Net-(Q39-Pad1)") (class "Default")
      (node (ref "Q39") (pin "1") (pinfunction "1_1") (pintype "input"))
      (node (ref "R39") (pin "2") (pinfunction "2_2") (pintype "unspecified"))
    )
    (net (code "116") (name "Net-(U00-LED1)") (class "Default")
      (node (ref "R01") (pin "2") (pinfunction "2_2") (pintype "unspecified"))
      (node (ref "U00") (pin "7") (pinfunction "LED1_7") (pintype "unspecified"))
    )
    (net (code "117") (name "Net-(U00-LED2)") (class "Default")
      (node (ref "R04") (pin "2") (pinfunction "2_2") (pintype "unspecified"))
      (node (ref "U00") (pin "8") (pinfunction "LED2_8") (pintype "unspecified"))
    )
    (net (code "118") (name "Net-(U00-LED3)") (class "Default")
      (node (ref "R02") (pin "2") (pinfunction "2_2") (pintype "unspecified"))
      (node (ref "U00") (pin "9") (pinfunction "LED3_9") (pintype "unspecified"))
    )
    (net (code "119") (name "Net-(U00-LED5)") (class "Default")
      (node (ref "R00") (pin "2") (pinfunction "2_2") (pintype "unspecified"))
      (node (ref "U00") (pin "11") (pinfunction "LED5_11") (pintype "unspecified"))
    )
    (net (code "120") (name "Net-(U00-LED6)") (class "Default")
      (node (ref "R06") (pin "2") (pinfunction "2_2") (pintype "unspecified"))
      (node (ref "U00") (pin "12") (pinfunction "LED6_12") (pintype "unspecified"))
    )
    (net (code "121") (name "Net-(U00-LED10)") (class "Default")
      (node (ref "R03") (pin "1") (pinfunction "1_1") (pintype "unspecified"))
      (node (ref "U00") (pin "17") (pinfunction "LED10_17") (pintype "unspecified"))
    )
    (net (code "122") (name "Net-(U00-LED11)") (class "Default")
      (node (ref "R07") (pin "1") (pinfunction "1_1") (pintype "unspecified"))
      (node (ref "U00") (pin "18") (pinfunction "LED11_18") (pintype "unspecified"))
    )
    (net (code "123") (name "Net-(U00-LED13)") (class "Default")
      (node (ref "R05") (pin "1") (pinfunction "1_1") (pintype "unspecified"))
      (node (ref "U00") (pin "20") (pinfunction "LED13_20") (pintype "unspecified"))
    )
    (net (code "124") (name "Net-(U00-LED14)") (class "Default")
      (node (ref "R09") (pin "1") (pinfunction "1_1") (pintype "unspecified"))
      (node (ref "U00") (pin "21") (pinfunction "LED14_21") (pintype "unspecified"))
    )
    (net (code "125") (name "Net-(U00-LED15)") (class "Default")
      (node (ref "R08") (pin "1") (pinfunction "1_1") (pintype "unspecified"))
      (node (ref "U00") (pin "22") (pinfunction "LED15_22") (pintype "unspecified"))
    )
    (net (code "126") (name "Net-(U10-LED1)") (class "Default")
      (node (ref "R11") (pin "2") (pinfunction "2_2") (pintype "unspecified"))
      (node (ref "U10") (pin "7") (pinfunction "LED1_7") (pintype "unspecified"))
    )
    (net (code "127") (name "Net-(U10-LED2)") (class "Default")
      (node (ref "R14") (pin "2") (pinfunction "2_2") (pintype "unspecified"))
      (node (ref "U10") (pin "8") (pinfunction "LED2_8") (pintype "unspecified"))
    )
    (net (code "128") (name "Net-(U10-LED3)") (class "Default")
      (node (ref "R12") (pin "2") (pinfunction "2_2") (pintype "unspecified"))
      (node (ref "U10") (pin "9") (pinfunction "LED3_9") (pintype "unspecified"))
    )
    (net (code "129") (name "Net-(U10-LED4)") (class "Default")
      (node (ref "R1L") (pin "2") (pinfunction "2_2") (pintype "unspecified"))
      (node (ref "U10") (pin "10") (pinfunction "LED4_10") (pintype "unspecified"))
    )
    (net (code "130") (name "Net-(U10-LED5)") (class "Default")
      (node (ref "R10") (pin "2") (pinfunction "2_2") (pintype "unspecified"))
      (node (ref "U10") (pin "11") (pinfunction "LED5_11") (pintype "unspecified"))
    )
    (net (code "131") (name "Net-(U10-LED6)") (class "Default")
      (node (ref "R16") (pin "2") (pinfunction "2_2") (pintype "unspecified"))
      (node (ref "U10") (pin "12") (pinfunction "LED6_12") (pintype "unspecified"))
    )
    (net (code "132") (name "Net-(U10-LED10)") (class "Default")
      (node (ref "R13") (pin "1") (pinfunction "1_1") (pintype "unspecified"))
      (node (ref "U10") (pin "17") (pinfunction "LED10_17") (pintype "unspecified"))
    )
    (net (code "133") (name "Net-(U10-LED11)") (class "Default")
      (node (ref "R17") (pin "1") (pinfunction "1_1") (pintype "unspecified"))
      (node (ref "U10") (pin "18") (pinfunction "LED11_18") (pintype "unspecified"))
    )
    (net (code "134") (name "Net-(U10-LED13)") (class "Default")
      (node (ref "R15") (pin "1") (pinfunction "1_1") (pintype "unspecified"))
      (node (ref "U10") (pin "20") (pinfunction "LED13_20") (pintype "unspecified"))
    )
    (net (code "135") (name "Net-(U10-LED14)") (class "Default")
      (node (ref "R19") (pin "1") (pinfunction "1_1") (pintype "unspecified"))
      (node (ref "U10") (pin "21") (pinfunction "LED14_21") (pintype "unspecified"))
    )
    (net (code "136") (name "Net-(U10-LED15)") (class "Default")
      (node (ref "R18") (pin "1") (pinfunction "1_1") (pintype "unspecified"))
      (node (ref "U10") (pin "22") (pinfunction "LED15_22") (pintype "unspecified"))
    )
    (net (code "137") (name "Net-(U20-LED1)") (class "Default")
      (node (ref "R21") (pin "2") (pinfunction "2_2") (pintype "unspecified"))
      (node (ref "U20") (pin "7") (pinfunction "LED1_7") (pintype "unspecified"))
    )
    (net (code "138") (name "Net-(U20-LED2)") (class "Default")
      (node (ref "R24") (pin "2") (pinfunction "2_2") (pintype "unspecified"))
      (node (ref "U20") (pin "8") (pinfunction "LED2_8") (pintype "unspecified"))
    )
    (net (code "139") (name "Net-(U20-LED3)") (class "Default")
      (node (ref "R22") (pin "2") (pinfunction "2_2") (pintype "unspecified"))
      (node (ref "U20") (pin "9") (pinfunction "LED3_9") (pintype "unspecified"))
    )
    (net (code "140") (name "Net-(U20-LED5)") (class "Default")
      (node (ref "R20") (pin "2") (pinfunction "2_2") (pintype "unspecified"))
      (node (ref "U20") (pin "11") (pinfunction "LED5_11") (pintype "unspecified"))
    )
    (net (code "141") (name "Net-(U20-LED6)") (class "Default")
      (node (ref "R26") (pin "2") (pinfunction "2_2") (pintype "unspecified"))
      (node (ref "U20") (pin "12") (pinfunction "LED6_12") (pintype "unspecified"))
    )
    (net (code "142") (name "Net-(U20-LED10)") (class "Default")
      (node (ref "R23") (pin "1") (pinfunction "1_1") (pintype "unspecified"))
      (node (ref "U20") (pin "17") (pinfunction "LED10_17") (pintype "unspecified"))
    )
    (net (code "143") (name "Net-(U20-LED11)") (class "Default")
      (node (ref "R27") (pin "1") (pinfunction "1_1") (pintype "unspecified"))
      (node (ref "U20") (pin "18") (pinfunction "LED11_18") (pintype "unspecified"))
    )
    (net (code "144") (name "Net-(U20-LED12)") (class "Default")
      (node (ref "R2R") (pin "1") (pinfunction "1_1") (pintype "unspecified"))
      (node (ref "U20") (pin "19") (pinfunction "LED12_19") (pintype "unspecified"))
    )
    (net (code "145") (name "Net-(U20-LED13)") (class "Default")
      (node (ref "R25") (pin "1") (pinfunction "1_1") (pintype "unspecified"))
      (node (ref "U20") (pin "20") (pinfunction "LED13_20") (pintype "unspecified"))
    )
    (net (code "146") (name "Net-(U20-LED14)") (class "Default")
      (node (ref "R29") (pin "1") (pinfunction "1_1") (pintype "unspecified"))
      (node (ref "U20") (pin "21") (pinfunction "LED14_21") (pintype "unspecified"))
    )
    (net (code "147") (name "Net-(U20-LED15)") (class "Default")
      (node (ref "R28") (pin "1") (pinfunction "1_1") (pintype "unspecified"))
      (node (ref "U20") (pin "22") (pinfunction "LED15_22") (pintype "unspecified"))
    )
    (net (code "148") (name "Net-(U30-LED1)") (class "Default")
      (node (ref "R31") (pin "2") (pinfunction "2_2") (pintype "unspecified"))
      (node (ref "U30") (pin "7") (pinfunction "LED1_7") (pintype "unspecified"))
    )
    (net (code "149") (name "Net-(U30-LED2)") (class "Default")
      (node (ref "R34") (pin "2") (pinfunction "2_2") (pintype "unspecified"))
      (node (ref "U30") (pin "8") (pinfunction "LED2_8") (pintype "unspecified"))
    )
    (net (code "150") (name "Net-(U30-LED3)") (class "Default")
      (node (ref "R32") (pin "2") (pinfunction "2_2") (pintype "unspecified"))
      (node (ref "U30") (pin "9") (pinfunction "LED3_9") (pintype "unspecified"))
    )
    (net (code "151") (name "Net-(U30-LED5)") (class "Default")
      (node (ref "R30") (pin "2") (pinfunction "2_2") (pintype "unspecified"))
      (node (ref "U30") (pin "11") (pinfunction "LED5_11") (pintype "unspecified"))
    )
    (net (code "152") (name "Net-(U30-LED6)") (class "Default")
      (node (ref "R36") (pin "2") (pinfunction "2_2") (pintype "unspecified"))
      (node (ref "U30") (pin "12") (pinfunction "LED6_12") (pintype "unspecified"))
    )
    (net (code "153") (name "Net-(U30-LED10)") (class "Default")
      (node (ref "R33") (pin "1") (pinfunction "1_1") (pintype "unspecified"))
      (node (ref "U30") (pin "17") (pinfunction "LED10_17") (pintype "unspecified"))
    )
    (net (code "154") (name "Net-(U30-LED11)") (class "Default")
      (node (ref "R37") (pin "1") (pinfunction "1_1") (pintype "unspecified"))
      (node (ref "U30") (pin "18") (pinfunction "LED11_18") (pintype "unspecified"))
    )
    (net (code "155") (name "Net-(U30-LED13)") (class "Default")
      (node (ref "R35") (pin "1") (pinfunction "1_1") (pintype "unspecified"))
      (node (ref "U30") (pin "20") (pinfunction "LED13_20") (pintype "unspecified"))
    )
    (net (code "156") (name "Net-(U30-LED14)") (class "Default")
      (node (ref "R39") (pin "1") (pinfunction "1_1") (pintype "unspecified"))
      (node (ref "U30") (pin "21") (pinfunction "LED14_21") (pintype "unspecified"))
    )
    (net (code "157") (name "Net-(U30-LED15)") (class "Default")
      (node (ref "R38") (pin "1") (pinfunction "1_1") (pintype "unspecified"))
      (node (ref "U30") (pin "22") (pinfunction "LED15_22") (pintype "unspecified"))
    )
    (net (code "158") (name "USB") (class "Default")
      (node (ref "H0") (pin "2") (pinfunction "2_2") (pintype "unspecified"))
      (node (ref "MPU0") (pin "26") (pinfunction "USB_26") (pintype "unspecified"))
    )
    (net (code "159") (name "unconnected-(CN0-Pad5)") (class "Default")
      (node (ref "CN0") (pin "5") (pinfunction "5_5") (pintype "unspecified+no_connect"))
    )
    (net (code "160") (name "unconnected-(CN0-Pad6)") (class "Default")
      (node (ref "CN0") (pin "6") (pinfunction "6_6") (pintype "unspecified+no_connect"))
    )
    (net (code "161") (name "unconnected-(D31-CKO-Pad5)") (class "Default")
      (node (ref "D31") (pin "5") (pinfunction "CKO_5") (pintype "unspecified+no_connect"))
    )
    (net (code "162") (name "unconnected-(D31-SDO-Pad6)") (class "Default")
      (node (ref "D31") (pin "6") (pinfunction "SDO_6") (pintype "unspecified+no_connect"))
    )
    (net (code "163") (name "unconnected-(MPU0-BAT-Pad28)") (class "Default")
      (node (ref "MPU0") (pin "28") (pinfunction "BAT_28") (pintype "unspecified+no_connect"))
    )
    (net (code "164") (name "unconnected-(MPU0-EN-Pad27)") (class "Default")
      (node (ref "MPU0") (pin "27") (pinfunction "EN_27") (pintype "unspecified+no_connect"))
    )
    (net (code "165") (name "unconnected-(MPU0-GPIO16-Pad14)") (class "Default")
      (node (ref "MPU0") (pin "14") (pinfunction "GPIO16_14") (pintype "unspecified+no_connect"))
    )
    (net (code "166") (name "unconnected-(MPU0-GPIO17-Pad15)") (class "Default")
      (node (ref "MPU0") (pin "15") (pinfunction "GPIO17_15") (pintype "unspecified+no_connect"))
    )
    (net (code "167") (name "unconnected-(MPU0-GPIO19-Pad13)") (class "Default")
      (node (ref "MPU0") (pin "13") (pinfunction "GPIO19_13") (pintype "unspecified+no_connect"))
    )
    (net (code "168") (name "unconnected-(MPU0-GPIO_12-Pad24)") (class "Default")
      (node (ref "MPU0") (pin "24") (pinfunction "GPIO_12_24") (pintype "unspecified+no_connect"))
    )
    (net (code "169") (name "unconnected-(MPU0-GPIO_15-Pad21)") (class "Default")
      (node (ref "MPU0") (pin "21") (pinfunction "GPIO_15_21") (pintype "unspecified+no_connect"))
    )
    (net (code "170") (name "unconnected-(MPU0-GPIO_21-Pad16)") (class "Default")
      (node (ref "MPU0") (pin "16") (pinfunction "GPIO_21_16") (pintype "unspecified+no_connect"))
    )
    (net (code "171") (name "unconnected-(MPU0-GPIO_22-Pad18)") (class "Default")
      (node (ref "MPU0") (pin "18") (pinfunction "GPIO_22_18") (pintype "unspecified+no_connect"))
    )
    (net (code "172") (name "unconnected-(MPU0-GPIO_25-Pad6)") (class "Default")
      (node (ref "MPU0") (pin "6") (pinfunction "GPIO_25_6") (pintype "unspecified+no_connect"))
    )
    (net (code "173") (name "unconnected-(MPU0-GPIO_26-Pad5)") (class "Default")
      (node (ref "MPU0") (pin "5") (pinfunction "GPIO_26_5") (pintype "unspecified+no_connect"))
    )
    (net (code "174") (name "unconnected-(MPU0-GPIO_32-Pad20)") (class "Default")
      (node (ref "MPU0") (pin "20") (pinfunction "GPIO_32_20") (pintype "unspecified+no_connect"))
    )
    (net (code "175") (name "unconnected-(MPU0-GPIO_34-Pad7)") (class "Default")
      (node (ref "MPU0") (pin "7") (pinfunction "GPIO_34_7") (pintype "unspecified+no_connect"))
    )
    (net (code "176") (name "unconnected-(MPU0-GPIO_36-Pad9)") (class "Default")
      (node (ref "MPU0") (pin "9") (pinfunction "GPIO_36_9") (pintype "unspecified+no_connect"))
    )
    (net (code "177") (name "unconnected-(MPU0-GPIO_39-Pad8)") (class "Default")
      (node (ref "MPU0") (pin "8") (pinfunction "GPIO_39_8") (pintype "unspecified+no_connect"))
    )
    (net (code "178") (name "unconnected-(MPU0-NC-Pad3)") (class "Default")
      (node (ref "MPU0") (pin "3") (pinfunction "NC_3") (pintype "unspecified+no_connect"))
    )
    (net (code "179") (name "unconnected-(MPU0-RST-Pad1)") (class "Default")
      (node (ref "MPU0") (pin "1") (pinfunction "RST_1") (pintype "unspecified+no_connect"))
    )
    (net (code "180") (name "unconnected-(MPU0-VSPI_MOSI-Pad17)") (class "Default")
      (node (ref "MPU0") (pin "17") (pinfunction "VSPI_MOSI_17") (pintype "unspecified+no_connect"))
    )
    (net (code "181") (name "unconnected-(MPU0-VSPI_SCLK-Pad12)") (class "Default")
      (node (ref "MPU0") (pin "12") (pinfunction "VSPI_SCLK_12") (pintype "unspecified+no_connect"))
    )
    (net (code "182") (name "unconnected-(PS+5V-EN-Pad10)") (class "Default")
      (node (ref "PS+5V") (pin "10") (pinfunction "EN_10") (pintype "unspecified+no_connect"))
    )
    (net (code "183") (name "unconnected-(PS+5V-VADJ-Pad6)") (class "Default")
      (node (ref "PS+5V") (pin "6") (pinfunction "VADJ_6") (pintype "unspecified+no_connect"))
    )
    (net (code "184") (name "unconnected-(U00-LED0-Pad6)") (class "Default")
      (node (ref "U00") (pin "6") (pinfunction "LED0_6") (pintype "unspecified+no_connect"))
    )
    (net (code "185") (name "unconnected-(U00-LED4-Pad10)") (class "Default")
      (node (ref "U00") (pin "10") (pinfunction "LED4_10") (pintype "unspecified+no_connect"))
    )
    (net (code "186") (name "unconnected-(U00-LED7-Pad13)") (class "Default")
      (node (ref "U00") (pin "13") (pinfunction "LED7_13") (pintype "unspecified+no_connect"))
    )
    (net (code "187") (name "unconnected-(U00-LED8-Pad15)") (class "Default")
      (node (ref "U00") (pin "15") (pinfunction "LED8_15") (pintype "unspecified+no_connect"))
    )
    (net (code "188") (name "unconnected-(U00-LED9-Pad16)") (class "Default")
      (node (ref "U00") (pin "16") (pinfunction "LED9_16") (pintype "unspecified+no_connect"))
    )
    (net (code "189") (name "unconnected-(U00-LED12-Pad19)") (class "Default")
      (node (ref "U00") (pin "19") (pinfunction "LED12_19") (pintype "unspecified+no_connect"))
    )
    (net (code "190") (name "unconnected-(U1-FTS-Pad5)") (class "Default")
      (node (ref "U1") (pin "5") (pinfunction "FTS_5") (pintype "unspecified+no_connect"))
    )
    (net (code "191") (name "unconnected-(U1-VSS-Pad6)") (class "Default")
      (node (ref "U1") (pin "6") (pinfunction "VSS_6") (pintype "unspecified+no_connect"))
    )
    (net (code "192") (name "unconnected-(U10-LED0-Pad6)") (class "Default")
      (node (ref "U10") (pin "6") (pinfunction "LED0_6") (pintype "unspecified+no_connect"))
    )
    (net (code "193") (name "unconnected-(U10-LED7-Pad13)") (class "Default")
      (node (ref "U10") (pin "13") (pinfunction "LED7_13") (pintype "unspecified+no_connect"))
    )
    (net (code "194") (name "unconnected-(U10-LED8-Pad15)") (class "Default")
      (node (ref "U10") (pin "15") (pinfunction "LED8_15") (pintype "unspecified+no_connect"))
    )
    (net (code "195") (name "unconnected-(U10-LED9-Pad16)") (class "Default")
      (node (ref "U10") (pin "16") (pinfunction "LED9_16") (pintype "unspecified+no_connect"))
    )
    (net (code "196") (name "unconnected-(U10-LED12-Pad19)") (class "Default")
      (node (ref "U10") (pin "19") (pinfunction "LED12_19") (pintype "unspecified+no_connect"))
    )
    (net (code "197") (name "unconnected-(U20-LED0-Pad6)") (class "Default")
      (node (ref "U20") (pin "6") (pinfunction "LED0_6") (pintype "unspecified+no_connect"))
    )
    (net (code "198") (name "unconnected-(U20-LED4-Pad10)") (class "Default")
      (node (ref "U20") (pin "10") (pinfunction "LED4_10") (pintype "unspecified+no_connect"))
    )
    (net (code "199") (name "unconnected-(U20-LED7-Pad13)") (class "Default")
      (node (ref "U20") (pin "13") (pinfunction "LED7_13") (pintype "unspecified+no_connect"))
    )
    (net (code "200") (name "unconnected-(U20-LED8-Pad15)") (class "Default")
      (node (ref "U20") (pin "15") (pinfunction "LED8_15") (pintype "unspecified+no_connect"))
    )
    (net (code "201") (name "unconnected-(U20-LED9-Pad16)") (class "Default")
      (node (ref "U20") (pin "16") (pinfunction "LED9_16") (pintype "unspecified+no_connect"))
    )
    (net (code "202") (name "unconnected-(U30-LED0-Pad6)") (class "Default")
      (node (ref "U30") (pin "6") (pinfunction "LED0_6") (pintype "unspecified+no_connect"))
    )
    (net (code "203") (name "unconnected-(U30-LED4-Pad10)") (class "Default")
      (node (ref "U30") (pin "10") (pinfunction "LED4_10") (pintype "unspecified+no_connect"))
    )
    (net (code "204") (name "unconnected-(U30-LED7-Pad13)") (class "Default")
      (node (ref "U30") (pin "13") (pinfunction "LED7_13") (pintype "unspecified+no_connect"))
    )
    (net (code "205") (name "unconnected-(U30-LED8-Pad15)") (class "Default")
      (node (ref "U30") (pin "15") (pinfunction "LED8_15") (pintype "unspecified+no_connect"))
    )
    (net (code "206") (name "unconnected-(U30-LED9-Pad16)") (class "Default")
      (node (ref "U30") (pin "16") (pinfunction "LED9_16") (pintype "unspecified+no_connect"))
    )
    (net (code "207") (name "unconnected-(U30-LED12-Pad19)") (class "Default")
      (node (ref "U30") (pin "19") (pinfunction "LED12_19") (pintype "unspecified+no_connect"))
    )
  )
)
